# leitorcartao.net
KiCad netlist of a schematic drawn in EAGLE
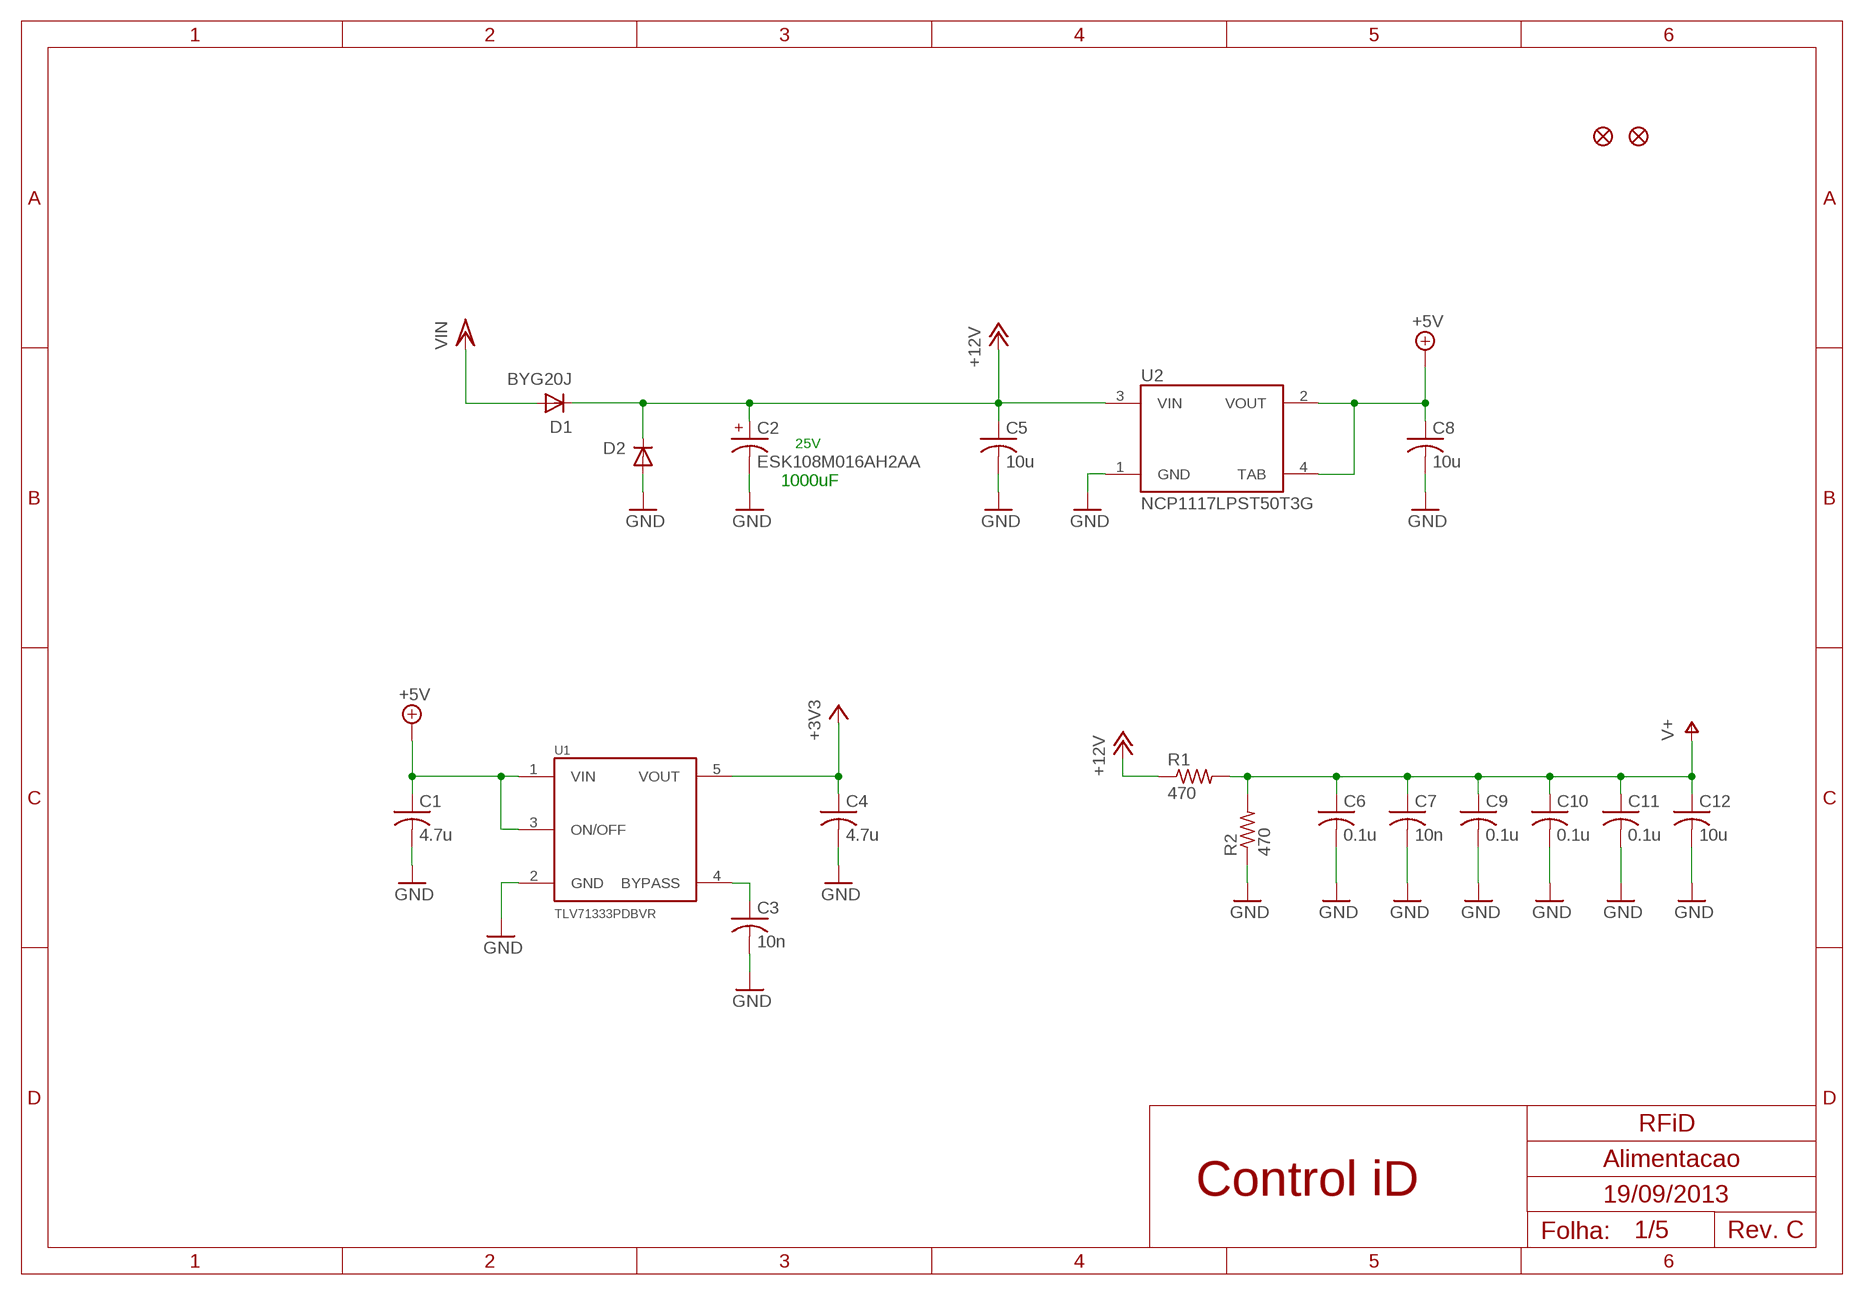
[diagram p0: schematic, sheet 1]
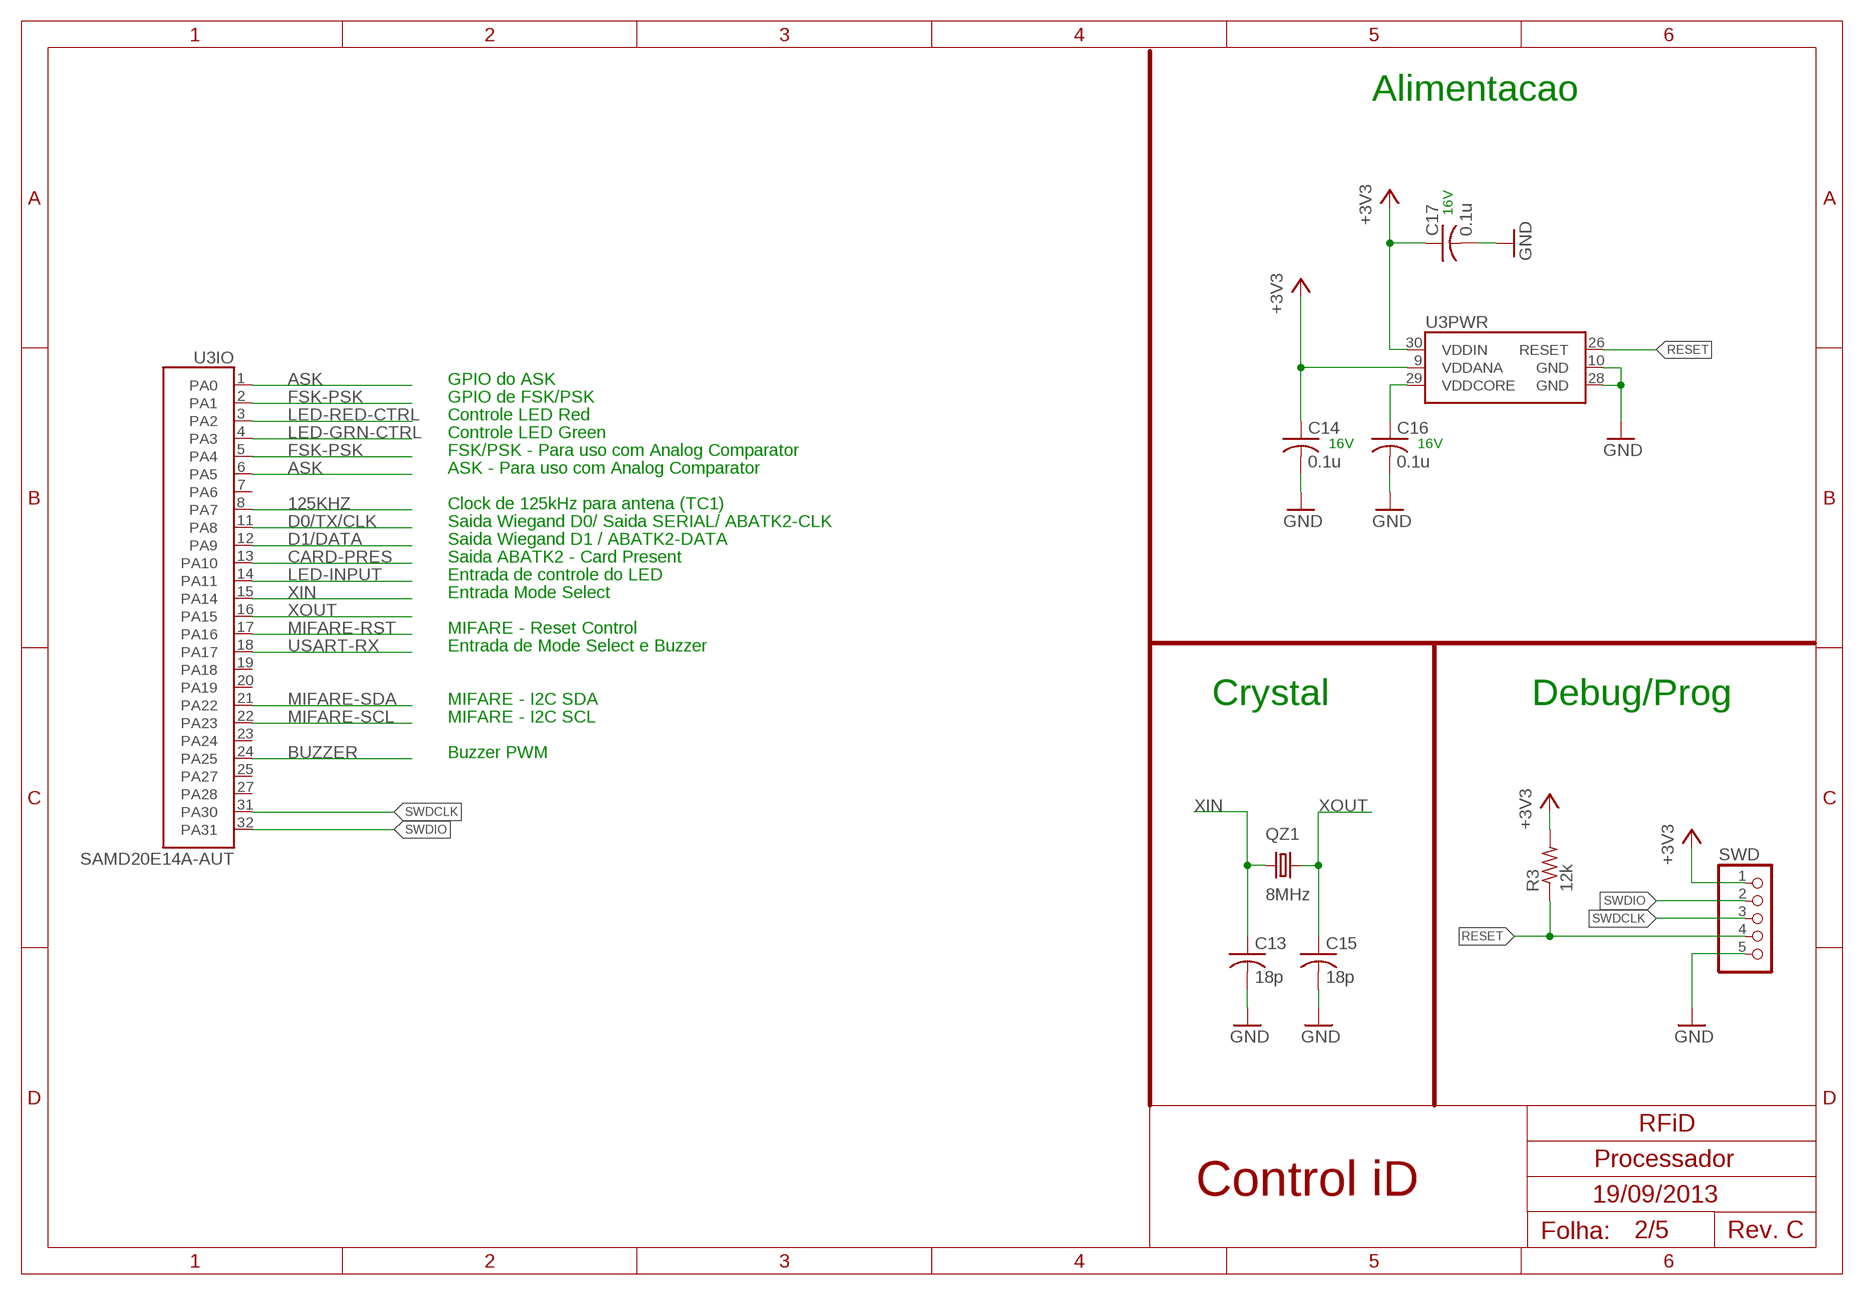
[diagram p1: schematic, sheet 2]
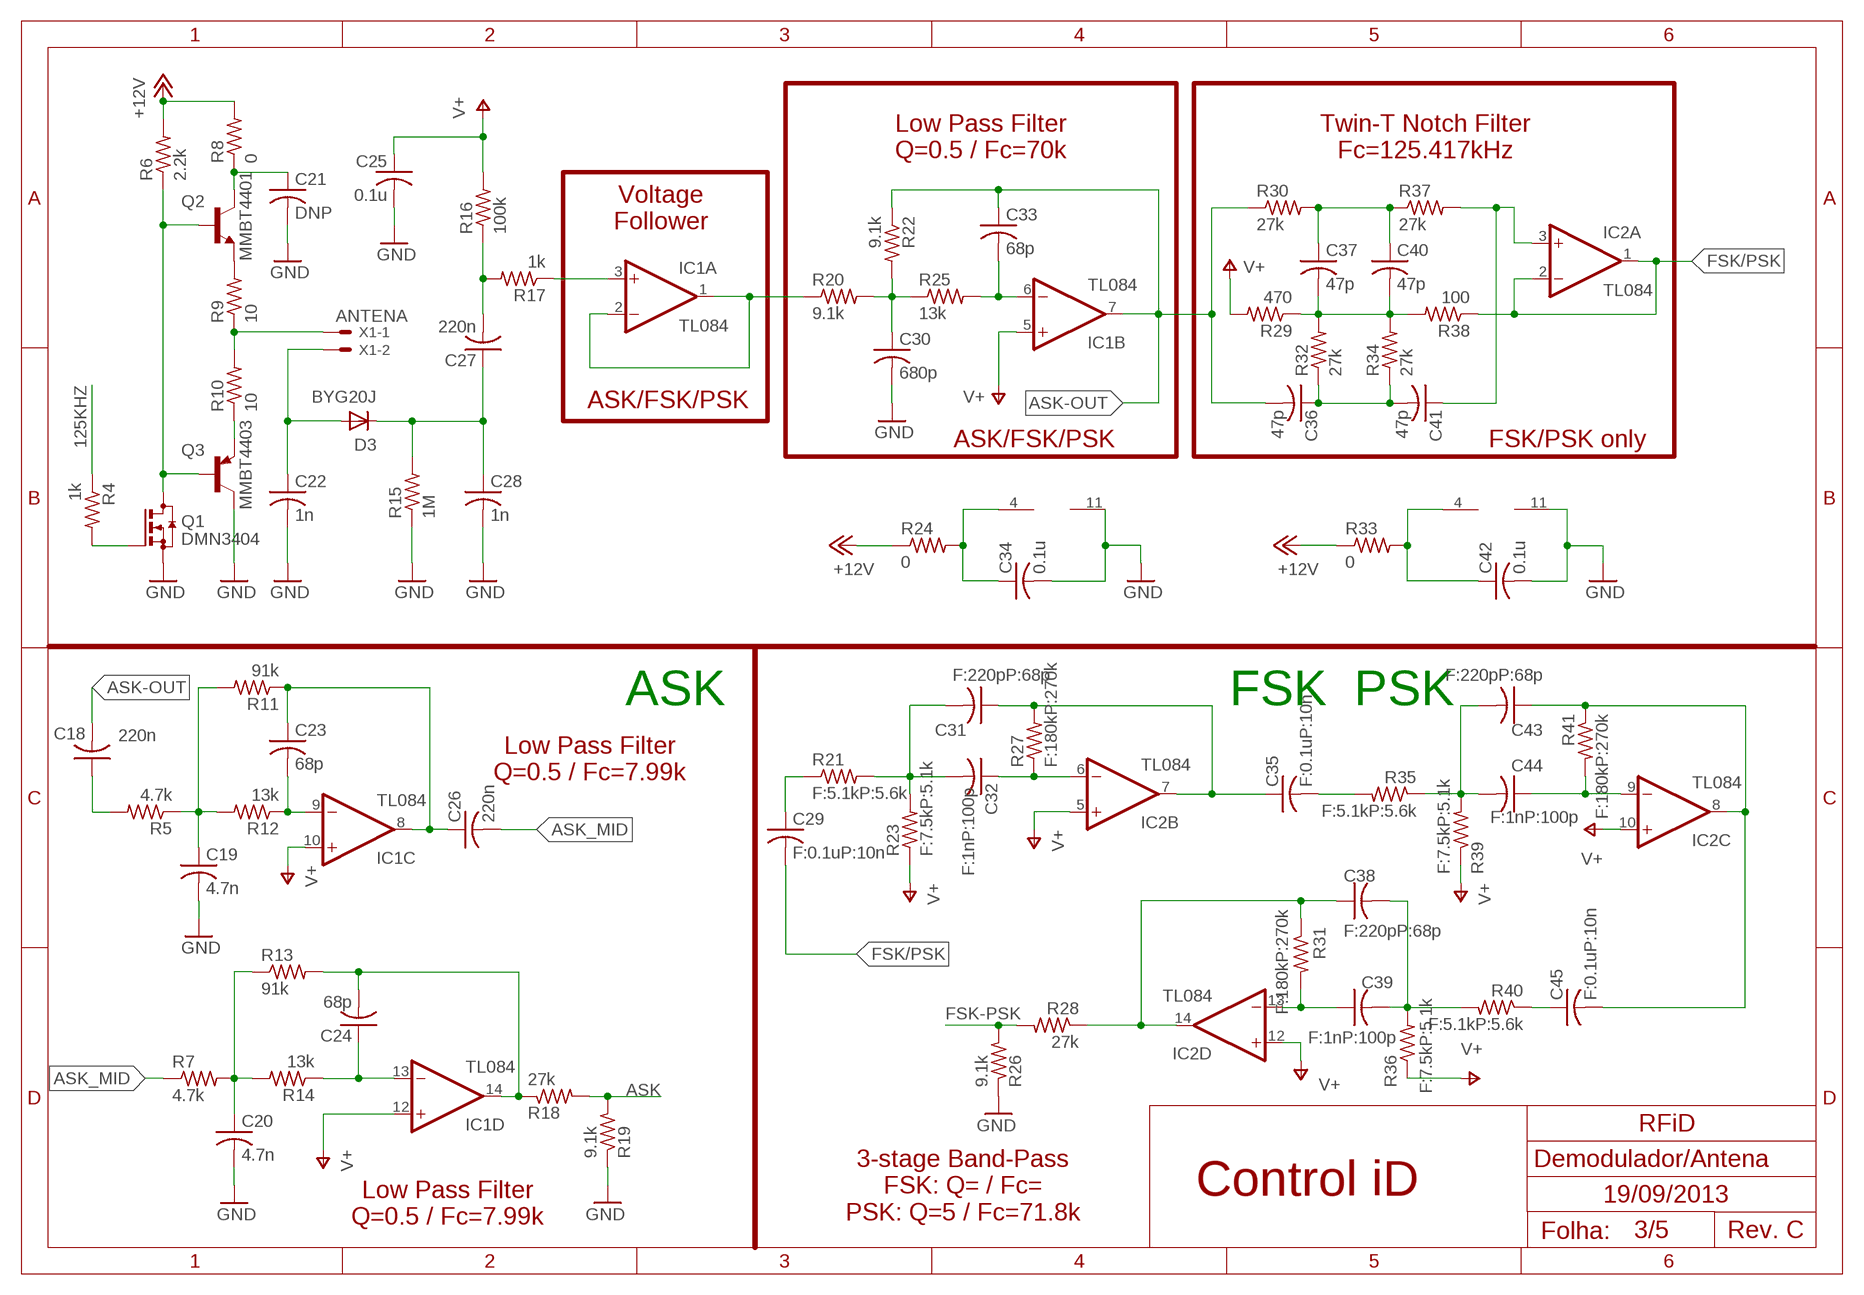
[diagram p2: schematic, sheet 3]
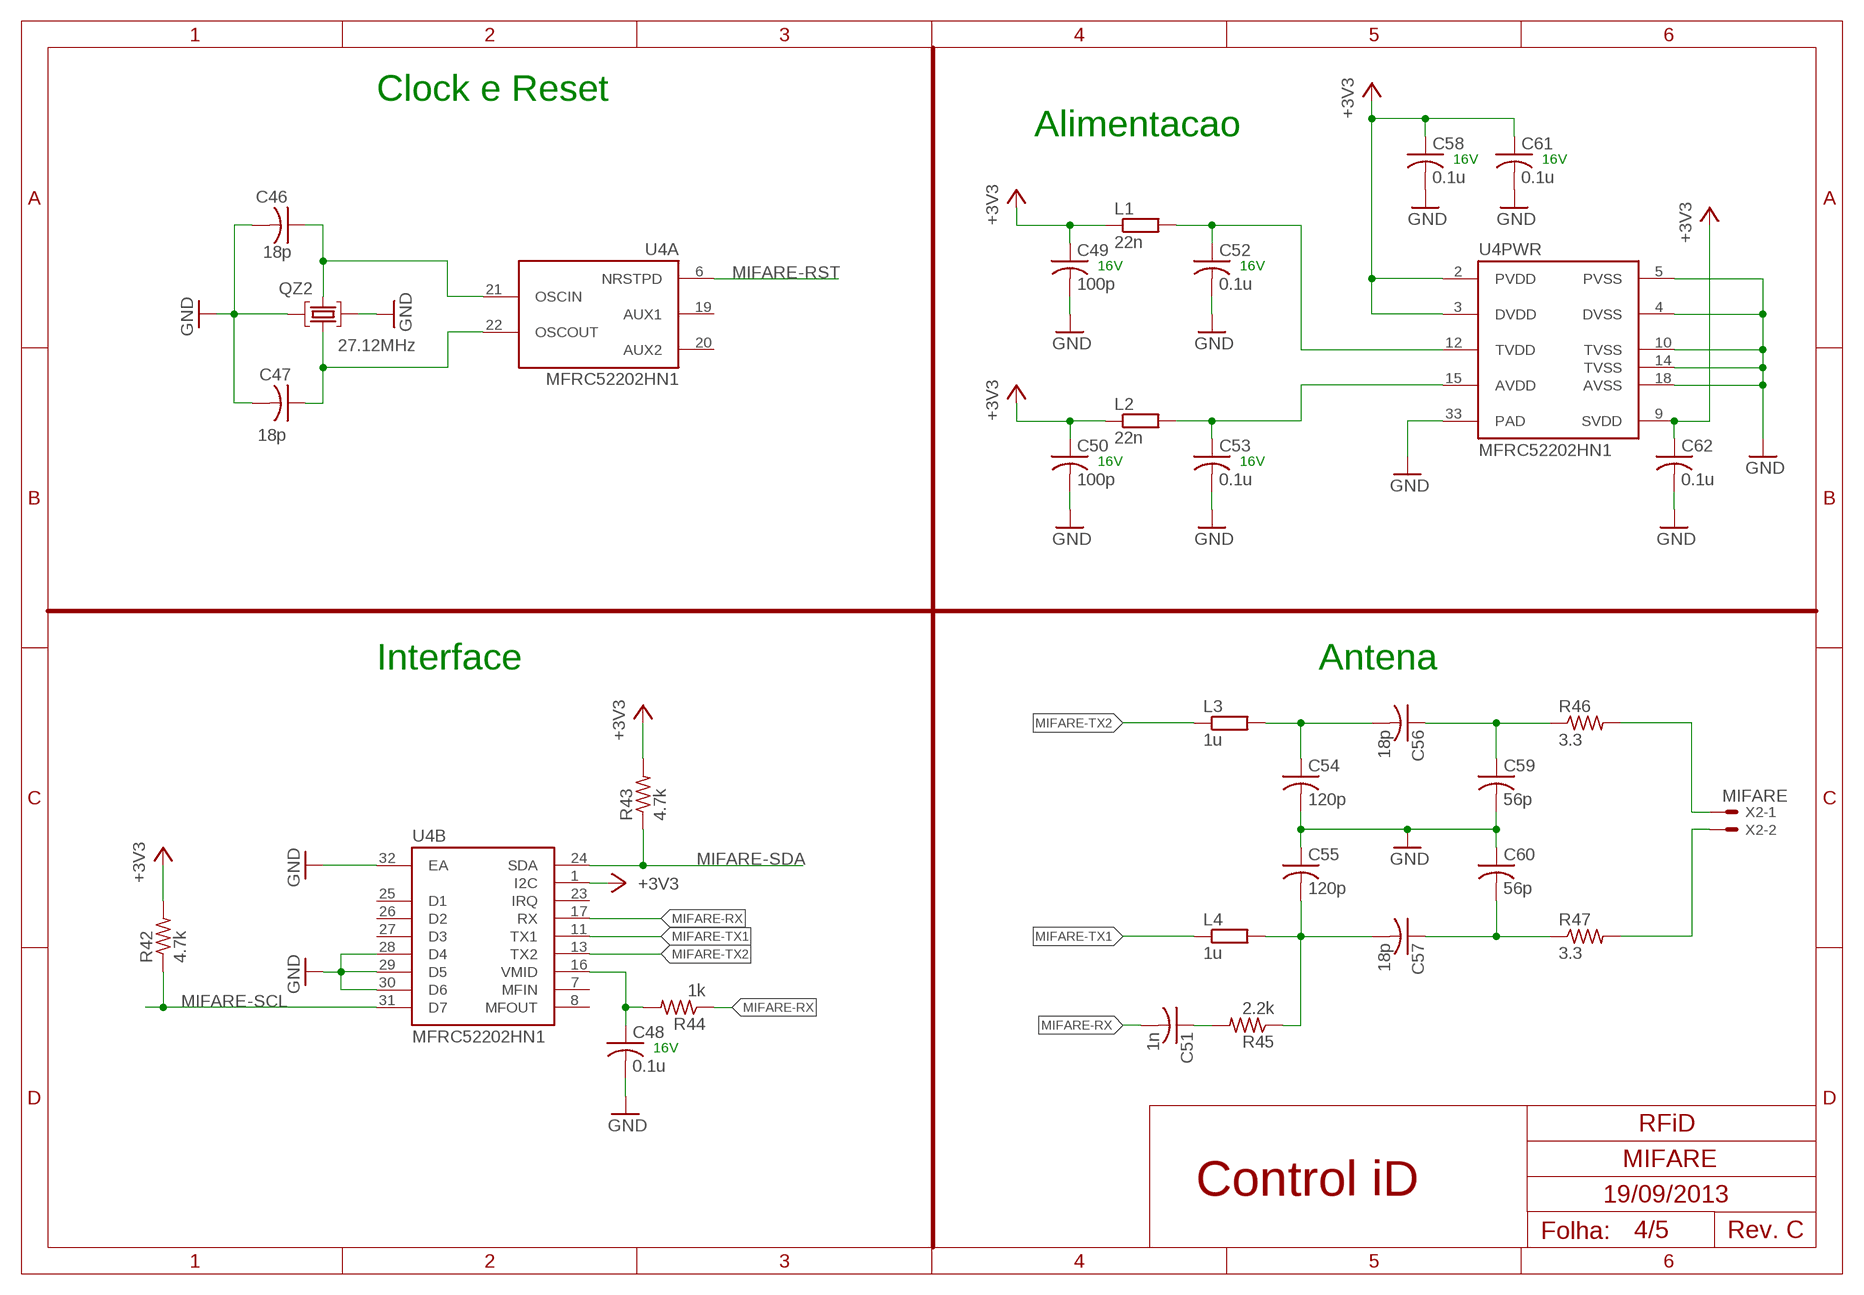
[diagram p3: schematic, sheet 4]
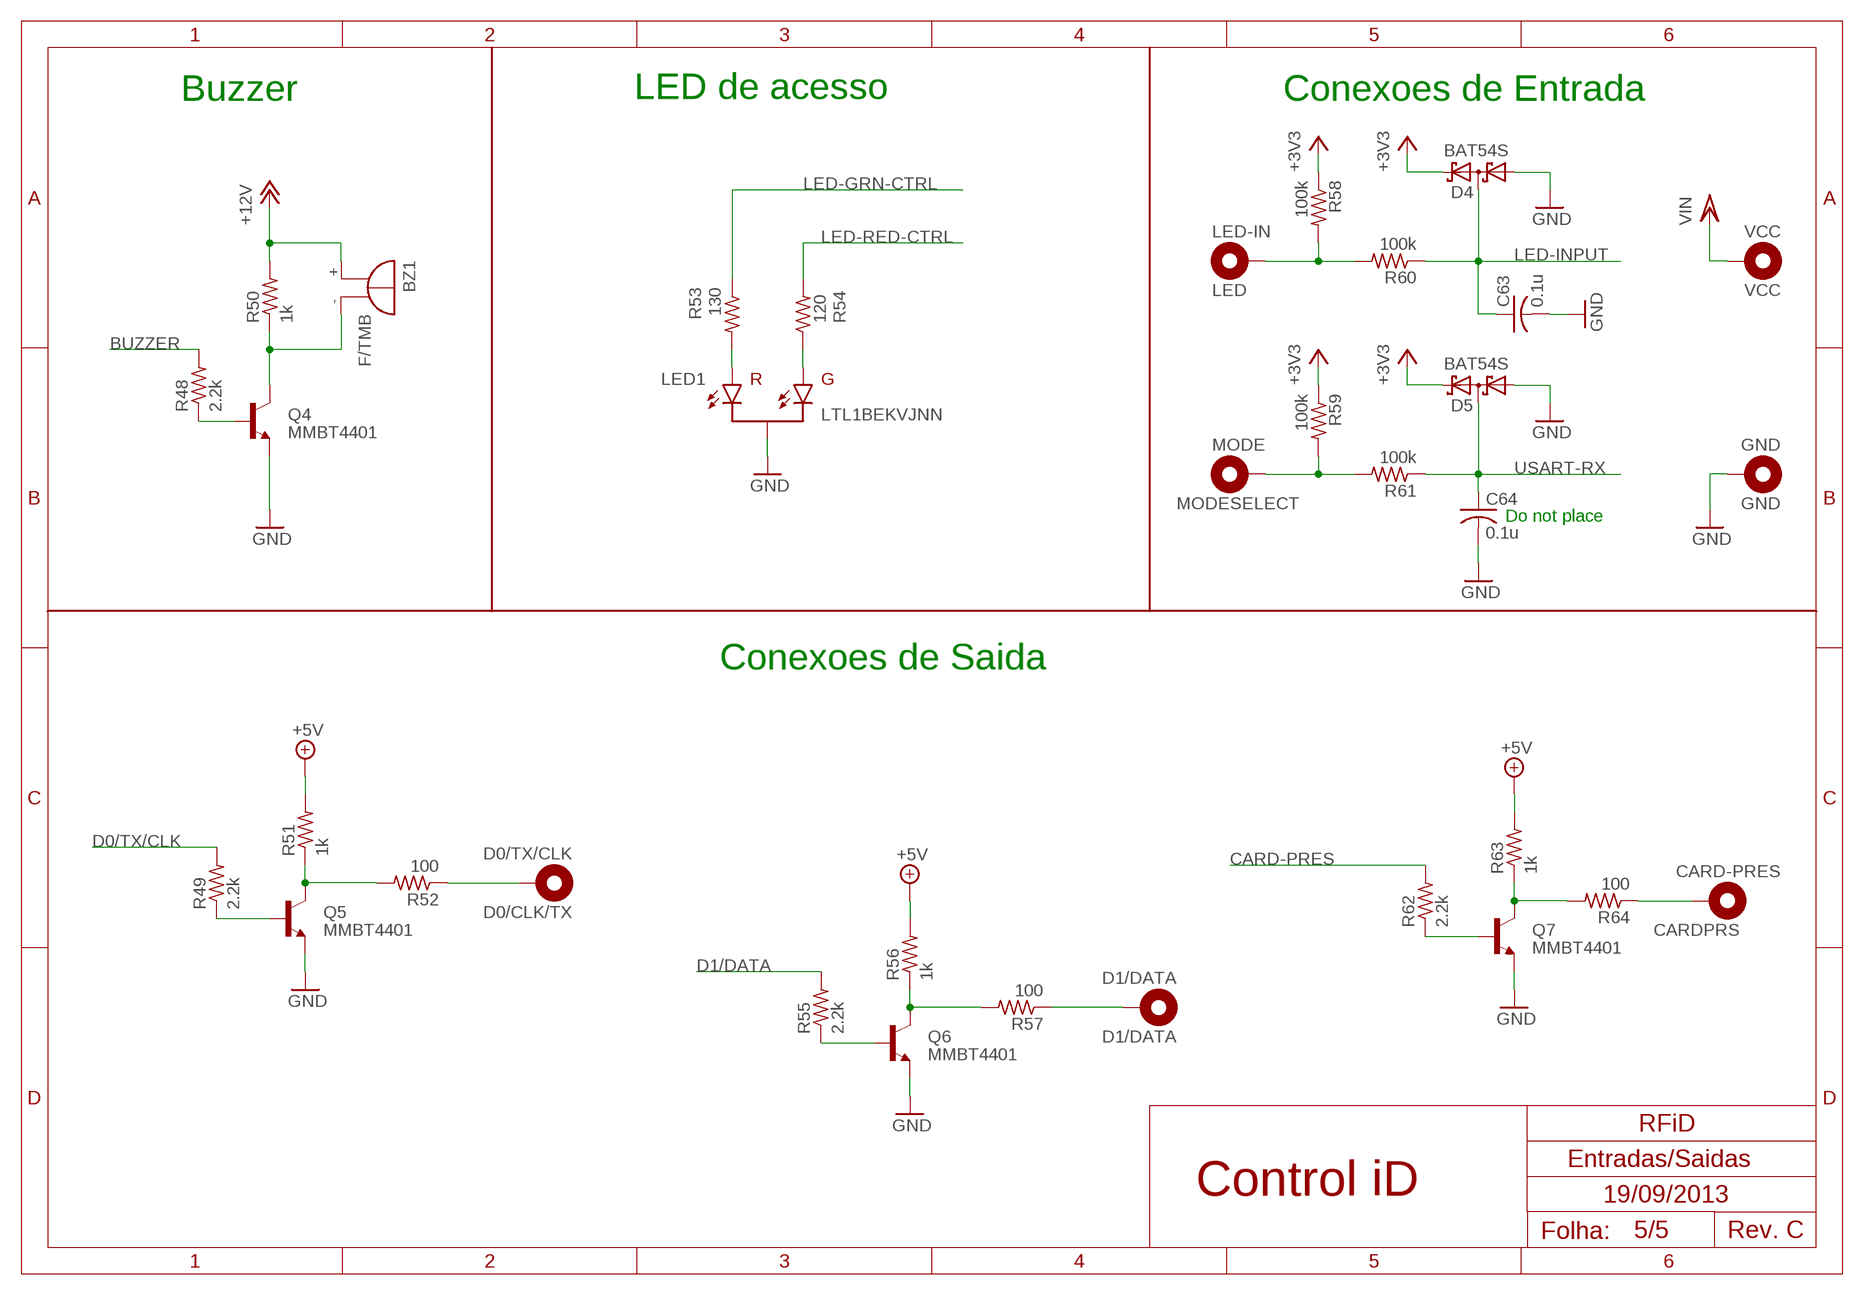
[diagram p4: schematic, sheet 5]

(export (version "E")
  (design (tool "Eeschema 10.0.6"))
  (components
    (comp (ref "BZ1")
      (value "F/TMB")
      (footprint "eagle-import:F_TMB")
      (libsource (lib "eagle-import") (part "F/TMB"))
    )
    (comp (ref "C63")
      (value "0.1u")
      (footprint "eagle-import:C0402")
      (libsource (lib "eagle-import") (part "C-USC0402"))
    )
    (comp (ref "C64")
      (value "0.1u")
      (footprint "eagle-import:C0402")
      (libsource (lib "eagle-import") (part "C-USC0402"))
    )
    (comp (ref "CARDPRS")
      (value "CARD-PRES")
      (footprint "eagle-import:HOLE")
      (libsource (lib "eagle-import") (part "PTHPAD"))
    )
    (comp (ref "D0/TX/CLK")
      (value "D0/CLK/TX")
      (footprint "eagle-import:HOLE")
      (libsource (lib "eagle-import") (part "PTHPAD"))
    )
    (comp (ref "D1/DATA")
      (value "D1/DATA")
      (footprint "eagle-import:HOLE")
      (libsource (lib "eagle-import") (part "PTHPAD"))
    )
    (comp (ref "D4")
      (value "BAT54S")
      (footprint "eagle-import:SOT23")
      (libsource (lib "eagle-import") (part "BAT54S"))
    )
    (comp (ref "D5")
      (value "BAT54S")
      (footprint "eagle-import:SOT23")
      (libsource (lib "eagle-import") (part "BAT54S"))
    )
    (comp (ref "GND")
      (value "GND")
      (footprint "eagle-import:HOLE")
      (libsource (lib "eagle-import") (part "PTHPAD"))
    )
    (comp (ref "LED-IN")
      (value "LED")
      (footprint "eagle-import:HOLE")
      (libsource (lib "eagle-import") (part "PTHPAD"))
    )
    (comp (ref "LED1")
      (value "LTL1BEKVJNN")
      (footprint "eagle-import:LTL1BEKVJNN")
      (libsource (lib "eagle-import") (part "LTL1BEKVJNN"))
    )
    (comp (ref "MODE")
      (value "MODESELECT")
      (footprint "eagle-import:HOLE")
      (libsource (lib "eagle-import") (part "PTHPAD"))
    )
    (comp (ref "Q4")
      (value "MMBT4401")
      (footprint "eagle-import:SOT23")
      (libsource (lib "eagle-import") (part "MMBT4401"))
    )
    (comp (ref "Q5")
      (value "MMBT4401")
      (footprint "eagle-import:SOT23")
      (libsource (lib "eagle-import") (part "MMBT4401"))
    )
    (comp (ref "Q6")
      (value "MMBT4401")
      (footprint "eagle-import:SOT23")
      (libsource (lib "eagle-import") (part "MMBT4401"))
    )
    (comp (ref "Q7")
      (value "MMBT4401")
      (footprint "eagle-import:SOT23")
      (libsource (lib "eagle-import") (part "MMBT4401"))
    )
    (comp (ref "R48")
      (value "2.2k")
      (footprint "eagle-import:R0402")
      (libsource (lib "eagle-import") (part "R-US_R0402"))
    )
    (comp (ref "R49")
      (value "2.2k")
      (footprint "eagle-import:R0402")
      (libsource (lib "eagle-import") (part "R-US_R0402"))
    )
    (comp (ref "R50")
      (value "1k")
      (footprint "eagle-import:R0402")
      (libsource (lib "eagle-import") (part "R-US_R0402"))
    )
    (comp (ref "R51")
      (value "1k")
      (footprint "eagle-import:R0402")
      (libsource (lib "eagle-import") (part "R-US_R0402"))
    )
    (comp (ref "R52")
      (value "100")
      (footprint "eagle-import:R0603")
      (libsource (lib "eagle-import") (part "R-US_R0603"))
    )
    (comp (ref "R53")
      (value "130")
      (footprint "eagle-import:R0402")
      (libsource (lib "eagle-import") (part "R-US_R0402"))
    )
    (comp (ref "R54")
      (value "120")
      (footprint "eagle-import:R0402")
      (libsource (lib "eagle-import") (part "R-US_R0402"))
    )
    (comp (ref "R55")
      (value "2.2k")
      (footprint "eagle-import:R0402")
      (libsource (lib "eagle-import") (part "R-US_R0402"))
    )
    (comp (ref "R56")
      (value "1k")
      (footprint "eagle-import:R0402")
      (libsource (lib "eagle-import") (part "R-US_R0402"))
    )
    (comp (ref "R57")
      (value "100")
      (footprint "eagle-import:R0603")
      (libsource (lib "eagle-import") (part "R-US_R0603"))
    )
    (comp (ref "R58")
      (value "100k")
      (footprint "eagle-import:R0603")
      (libsource (lib "eagle-import") (part "R-US_R0603"))
    )
    (comp (ref "R59")
      (value "100k")
      (footprint "eagle-import:R0603")
      (libsource (lib "eagle-import") (part "R-US_R0603"))
    )
    (comp (ref "R60")
      (value "100k")
      (footprint "eagle-import:R0603")
      (libsource (lib "eagle-import") (part "R-US_R0603"))
    )
    (comp (ref "R61")
      (value "100k")
      (footprint "eagle-import:R0603")
      (libsource (lib "eagle-import") (part "R-US_R0603"))
    )
    (comp (ref "R62")
      (value "2.2k")
      (footprint "eagle-import:R0402")
      (libsource (lib "eagle-import") (part "R-US_R0402"))
    )
    (comp (ref "R63")
      (value "1k")
      (footprint "eagle-import:R0402")
      (libsource (lib "eagle-import") (part "R-US_R0402"))
    )
    (comp (ref "R64")
      (value "100")
      (footprint "eagle-import:R0603")
      (libsource (lib "eagle-import") (part "R-US_R0603"))
    )
    (comp (ref "VCC")
      (value "VCC")
      (footprint "eagle-import:HOLE")
      (libsource (lib "eagle-import") (part "PTHPAD"))
    )
    (comp (ref "C46")
      (value "18p")
      (footprint "eagle-import:C0603")
      (libsource (lib "eagle-import") (part "C-USC0603"))
    )
    (comp (ref "C47")
      (value "18p")
      (footprint "eagle-import:C0603")
      (libsource (lib "eagle-import") (part "C-USC0603"))
    )
    (comp (ref "C48")
      (value "0.1u")
      (footprint "eagle-import:C0402")
      (libsource (lib "eagle-import") (part "C-USC0402"))
    )
    (comp (ref "C49")
      (value "100p")
      (footprint "eagle-import:C0402")
      (libsource (lib "eagle-import") (part "C-USC0402"))
    )
    (comp (ref "C50")
      (value "100p")
      (footprint "eagle-import:C0402")
      (libsource (lib "eagle-import") (part "C-USC0402"))
    )
    (comp (ref "C51")
      (value "1n")
      (footprint "eagle-import:C0402")
      (libsource (lib "eagle-import") (part "C-USC0402"))
    )
    (comp (ref "C52")
      (value "0.1u")
      (footprint "eagle-import:C0402")
      (libsource (lib "eagle-import") (part "C-USC0402"))
    )
    (comp (ref "C53")
      (value "0.1u")
      (footprint "eagle-import:C0402")
      (libsource (lib "eagle-import") (part "C-USC0402"))
    )
    (comp (ref "C54")
      (value "120p")
      (footprint "eagle-import:C0603")
      (libsource (lib "eagle-import") (part "C-USC0603"))
    )
    (comp (ref "C55")
      (value "120p")
      (footprint "eagle-import:C0603")
      (libsource (lib "eagle-import") (part "C-USC0603"))
    )
    (comp (ref "C56")
      (value "18p")
      (footprint "eagle-import:C0603")
      (libsource (lib "eagle-import") (part "C-USC0603"))
    )
    (comp (ref "C57")
      (value "18p")
      (footprint "eagle-import:C0603")
      (libsource (lib "eagle-import") (part "C-USC0603"))
    )
    (comp (ref "C58")
      (value "0.1u")
      (footprint "eagle-import:C0402")
      (libsource (lib "eagle-import") (part "C-USC0402"))
    )
    (comp (ref "C59")
      (value "56p")
      (footprint "eagle-import:C0603")
      (libsource (lib "eagle-import") (part "C-USC0603"))
    )
    (comp (ref "C60")
      (value "56p")
      (footprint "eagle-import:C0603")
      (libsource (lib "eagle-import") (part "C-USC0603"))
    )
    (comp (ref "C61")
      (value "0.1u")
      (footprint "eagle-import:C0402")
      (libsource (lib "eagle-import") (part "C-USC0402"))
    )
    (comp (ref "C62")
      (value "0.1u")
      (footprint "eagle-import:C0402")
      (libsource (lib "eagle-import") (part "C-USC0402"))
    )
    (comp (ref "L1")
      (value "22n")
      (footprint "eagle-import:R0402")
      (libsource (lib "eagle-import") (part "R-EU_R0402"))
    )
    (comp (ref "L2")
      (value "22n")
      (footprint "eagle-import:R0402")
      (libsource (lib "eagle-import") (part "R-EU_R0402"))
    )
    (comp (ref "L3")
      (value "1u")
      (footprint "eagle-import:R0603")
      (libsource (lib "eagle-import") (part "R-EU_R0603"))
    )
    (comp (ref "L4")
      (value "1u")
      (footprint "eagle-import:R0603")
      (libsource (lib "eagle-import") (part "R-EU_R0603"))
    )
    (comp (ref "QZ2")
      (value "27.12MHz")
      (footprint "eagle-import:CRISTAL4SMD")
      (libsource (lib "eagle-import") (part "CRISTAL"))
    )
    (comp (ref "R42")
      (value "4.7k")
      (footprint "eagle-import:R0402")
      (libsource (lib "eagle-import") (part "R-US_R0402"))
    )
    (comp (ref "R43")
      (value "4.7k")
      (footprint "eagle-import:R0402")
      (libsource (lib "eagle-import") (part "R-US_R0402"))
    )
    (comp (ref "R44")
      (value "1k")
      (footprint "eagle-import:R0402")
      (libsource (lib "eagle-import") (part "R-US_R0402"))
    )
    (comp (ref "R45")
      (value "2.2k")
      (footprint "eagle-import:R0402")
      (libsource (lib "eagle-import") (part "R-US_R0402"))
    )
    (comp (ref "R46")
      (value "3.3")
      (footprint "eagle-import:R0603")
      (libsource (lib "eagle-import") (part "R-US_R0603"))
    )
    (comp (ref "R47")
      (value "3.3")
      (footprint "eagle-import:R0603")
      (libsource (lib "eagle-import") (part "R-US_R0603"))
    )
    (comp (ref "U4")
      (value "MFRC52202HN1")
      (footprint "eagle-import:QFN32")
      (fields
        (field (name "MIFARE") "X")
        (field (name "MIFARE_CUSTOMERPN") "IC/MFRC52202")
        (field (name "MIFARE_PN") "MFRC52202HN1,151")
      )
      (libsource (lib "eagle-import") (part "MFRC52202HN1"))
    )
    (comp (ref "X2")
      (value "MIFARE")
      (footprint "eagle-import:ANTENNA")
      (libsource (lib "eagle-import") (part "ANTENA"))
    )
    (comp (ref "C1")
      (value "4.7u")
      (footprint "eagle-import:C0603")
      (libsource (lib "eagle-import") (part "C-USC0603"))
    )
    (comp (ref "C2")
      (value "ESK108M016AH2AA")
      (footprint "eagle-import:ESK108M016AH2AA")
      (libsource (lib "eagle-import") (part "ESK108M016AH2AA"))
    )
    (comp (ref "C3")
      (value "10n")
      (footprint "eagle-import:C0402")
      (libsource (lib "eagle-import") (part "C-USC0402"))
    )
    (comp (ref "C4")
      (value "4.7u")
      (footprint "eagle-import:C0603")
      (libsource (lib "eagle-import") (part "C-USC0603"))
    )
    (comp (ref "C5")
      (value "10u")
      (footprint "eagle-import:C0805")
      (libsource (lib "eagle-import") (part "C-USC0805"))
    )
    (comp (ref "C6")
      (value "0.1u")
      (footprint "eagle-import:C0402")
      (libsource (lib "eagle-import") (part "C-USC0402"))
    )
    (comp (ref "C7")
      (value "10n")
      (footprint "eagle-import:C0402")
      (libsource (lib "eagle-import") (part "C-USC0402"))
    )
    (comp (ref "C8")
      (value "10u")
      (footprint "eagle-import:C0805")
      (libsource (lib "eagle-import") (part "C-USC0805"))
    )
    (comp (ref "C9")
      (value "0.1u")
      (footprint "eagle-import:C0402")
      (libsource (lib "eagle-import") (part "C-USC0402"))
    )
    (comp (ref "C10")
      (value "0.1u")
      (footprint "eagle-import:C0402")
      (libsource (lib "eagle-import") (part "C-USC0402"))
    )
    (comp (ref "C11")
      (value "0.1u")
      (footprint "eagle-import:C0402")
      (libsource (lib "eagle-import") (part "C-USC0402"))
    )
    (comp (ref "C12")
      (value "10u")
      (footprint "eagle-import:C0805")
      (libsource (lib "eagle-import") (part "C-USC0805"))
    )
    (comp (ref "D1")
      (value "BYG20J")
      (footprint "eagle-import:SMA")
      (libsource (lib "eagle-import") (part "BYG20J"))
    )
    (comp (ref "D2")
      (value "DIODE-DO214AC")
      (footprint "eagle-import:DO214AC")
      (libsource (lib "eagle-import") (part "DIODE-DO214AC"))
    )
    (comp (ref "FID1")
      (value "FIDUCIAL1.5X3")
      (footprint "eagle-import:FIDUCIAL-1.5X3")
      (libsource (lib "eagle-import") (part "FIDUCIAL1.5X3"))
    )
    (comp (ref "FID3")
      (value "FIDUCIAL1.5X3")
      (footprint "eagle-import:FIDUCIAL-1.5X3")
      (libsource (lib "eagle-import") (part "FIDUCIAL1.5X3"))
    )
    (comp (ref "R1")
      (value "470")
      (footprint "eagle-import:R0402")
      (libsource (lib "eagle-import") (part "R-US_R0402"))
    )
    (comp (ref "R2")
      (value "470")
      (footprint "eagle-import:R0402")
      (libsource (lib "eagle-import") (part "R-US_R0402"))
    )
    (comp (ref "U1")
      (value "TLV71333PDBVR")
      (footprint "eagle-import:SOT-23-5")
      (libsource (lib "eagle-import") (part "LP2985-33DBVR"))
    )
    (comp (ref "U2")
      (value "NCP1117LPST50T3G")
      (footprint "eagle-import:SOT223-3L")
      (libsource (lib "eagle-import") (part "TLV1117-50CDCYR"))
    )
    (comp (ref "C18")
      (value "220n")
      (footprint "eagle-import:C0402")
      (libsource (lib "eagle-import") (part "C-USC0402"))
    )
    (comp (ref "C19")
      (value "4.7n")
      (footprint "eagle-import:C0402")
      (libsource (lib "eagle-import") (part "C-USC0402"))
    )
    (comp (ref "C20")
      (value "4.7n")
      (footprint "eagle-import:C0402")
      (libsource (lib "eagle-import") (part "C-USC0402"))
    )
    (comp (ref "C21")
      (value "DNP")
      (footprint "eagle-import:C0603")
      (libsource (lib "eagle-import") (part "C-USC0603"))
    )
    (comp (ref "C22")
      (value "1n")
      (footprint "eagle-import:C1812S")
      (libsource (lib "eagle-import") (part "C-USC1812S"))
    )
    (comp (ref "C23")
      (value "68p")
      (footprint "eagle-import:C0402")
      (libsource (lib "eagle-import") (part "C-USC0402"))
    )
    (comp (ref "C24")
      (value "68p")
      (footprint "eagle-import:C0402")
      (libsource (lib "eagle-import") (part "C-USC0402"))
    )
    (comp (ref "C25")
      (value "0.1u")
      (footprint "eagle-import:C0402")
      (libsource (lib "eagle-import") (part "C-USC0402"))
    )
    (comp (ref "C26")
      (value "220n")
      (footprint "eagle-import:C0402")
      (libsource (lib "eagle-import") (part "C-USC0402"))
    )
    (comp (ref "C27")
      (value "220n")
      (footprint "eagle-import:C1206S")
      (libsource (lib "eagle-import") (part "C-USC1206S"))
    )
    (comp (ref "C28")
      (value "1n")
      (footprint "eagle-import:C1206S")
      (libsource (lib "eagle-import") (part "C-USC1206S"))
    )
    (comp (ref "C29")
      (value "F:0.1uP:10n")
      (footprint "eagle-import:C0402")
      (libsource (lib "eagle-import") (part "C-USC0402"))
    )
    (comp (ref "C30")
      (value "680p")
      (footprint "eagle-import:C0402")
      (libsource (lib "eagle-import") (part "C-USC0402"))
    )
    (comp (ref "C31")
      (value "F:220pP:68p")
      (footprint "eagle-import:C0402")
      (libsource (lib "eagle-import") (part "C-USC0402"))
    )
    (comp (ref "C32")
      (value "F:1nP:100p")
      (footprint "eagle-import:C0402")
      (libsource (lib "eagle-import") (part "C-USC0402"))
    )
    (comp (ref "C33")
      (value "68p")
      (footprint "eagle-import:C0402")
      (libsource (lib "eagle-import") (part "C-USC0402"))
    )
    (comp (ref "C34")
      (value "0.1u")
      (footprint "eagle-import:C0402")
      (libsource (lib "eagle-import") (part "C-USC0402"))
    )
    (comp (ref "C35")
      (value "F:0.1uP:10n")
      (footprint "eagle-import:C0402")
      (libsource (lib "eagle-import") (part "C-USC0402"))
    )
    (comp (ref "C36")
      (value "47p")
      (footprint "eagle-import:C0402")
      (libsource (lib "eagle-import") (part "C-USC0402"))
    )
    (comp (ref "C37")
      (value "47p")
      (footprint "eagle-import:C0402")
      (libsource (lib "eagle-import") (part "C-USC0402"))
    )
    (comp (ref "C38")
      (value "F:220pP:68p")
      (footprint "eagle-import:C0402")
      (libsource (lib "eagle-import") (part "C-USC0402"))
    )
    (comp (ref "C39")
      (value "F:1nP:100p")
      (footprint "eagle-import:C0402")
      (libsource (lib "eagle-import") (part "C-USC0402"))
    )
    (comp (ref "C40")
      (value "47p")
      (footprint "eagle-import:C0402")
      (libsource (lib "eagle-import") (part "C-USC0402"))
    )
    (comp (ref "C41")
      (value "47p")
      (footprint "eagle-import:C0402")
      (libsource (lib "eagle-import") (part "C-USC0402"))
    )
    (comp (ref "C42")
      (value "0.1u")
      (footprint "eagle-import:C0402")
      (libsource (lib "eagle-import") (part "C-USC0402"))
    )
    (comp (ref "C43")
      (value "F:220pP:68p")
      (footprint "eagle-import:C0402")
      (libsource (lib "eagle-import") (part "C-USC0402"))
    )
    (comp (ref "C44")
      (value "F:1nP:100p")
      (footprint "eagle-import:C0402")
      (libsource (lib "eagle-import") (part "C-USC0402"))
    )
    (comp (ref "C45")
      (value "F:0.1uP:10n")
      (footprint "eagle-import:C0402")
      (libsource (lib "eagle-import") (part "C-USC0402"))
    )
    (comp (ref "D3")
      (value "BYG20J")
      (footprint "eagle-import:SMA")
      (libsource (lib "eagle-import") (part "BYG20J"))
    )
    (comp (ref "IC1")
      (value "TL084")
      (footprint "eagle-import:TSSOP14")
      (fields
        (field (name "ASK") "X")
        (field (name "ASK_CUSTOMERPN") "IC/TL084/TSSOP14")
        (field (name "ASK_PN") "TL084CPT")
        (field (name "FSK") "X")
        (field (name "FSK_CUSTOMERPN") "IC/TL084/TSSOP14")
        (field (name "FSK_PN") "TL084CPT")
        (field (name "MIFARE") "X")
        (field (name "MIFARE_CUSTOMERPN") "IC/TL084/TSSOP14")
        (field (name "MIFARE_PN") "TL084CPT")
        (field (name "PSK") "X")
        (field (name "PSK_CUSTOMERPN") "IC/TL084/TSSOP14")
        (field (name "PSK_PN") "TL084CPT")
      )
      (libsource (lib "eagle-import") (part "TL084"))
    )
    (comp (ref "IC2")
      (value "TL084")
      (footprint "eagle-import:TSSOP14")
      (fields
        (field (name "FSK") "X")
        (field (name "FSK_CUSTOMERPN") "IC/TL084/TSSOP14")
        (field (name "FSK_PN") "TL084CPT")
        (field (name "PSK") "X")
        (field (name "PSK_CUSTOMERPN") "IC/TL084/TSSOP14")
        (field (name "PSK_PN") "TL084CPT")
      )
      (libsource (lib "eagle-import") (part "TL084"))
    )
    (comp (ref "Q1")
      (value "DMN3404")
      (footprint "eagle-import:SOT23")
      (libsource (lib "eagle-import") (part "DMN3404"))
    )
    (comp (ref "Q2")
      (value "MMBT4401")
      (footprint "eagle-import:SOT23")
      (libsource (lib "eagle-import") (part "MMBT4401"))
    )
    (comp (ref "Q3")
      (value "MMBT4403")
      (footprint "eagle-import:SOT23")
      (libsource (lib "eagle-import") (part "MMBT4403"))
    )
    (comp (ref "R4")
      (value "1k")
      (footprint "eagle-import:R0402")
      (libsource (lib "eagle-import") (part "R-US_R0402"))
    )
    (comp (ref "R5")
      (value "4.7k")
      (footprint "eagle-import:R0402")
      (libsource (lib "eagle-import") (part "R-US_R0402"))
    )
    (comp (ref "R6")
      (value "2.2k")
      (footprint "eagle-import:R0402")
      (libsource (lib "eagle-import") (part "R-US_R0402"))
    )
    (comp (ref "R7")
      (value "4.7k")
      (footprint "eagle-import:R0402")
      (libsource (lib "eagle-import") (part "R-US_R0402"))
    )
    (comp (ref "R8")
      (value "0")
      (footprint "eagle-import:R0402")
      (libsource (lib "eagle-import") (part "R-US_R0402"))
    )
    (comp (ref "R9")
      (value "10")
      (footprint "eagle-import:R0603")
      (libsource (lib "eagle-import") (part "R-US_R0603"))
    )
    (comp (ref "R10")
      (value "10")
      (footprint "eagle-import:R0603")
      (libsource (lib "eagle-import") (part "R-US_R0603"))
    )
    (comp (ref "R11")
      (value "91k")
      (footprint "eagle-import:R0402")
      (libsource (lib "eagle-import") (part "R-US_R0402"))
    )
    (comp (ref "R12")
      (value "13k")
      (footprint "eagle-import:R0402")
      (libsource (lib "eagle-import") (part "R-US_R0402"))
    )
    (comp (ref "R13")
      (value "91k")
      (footprint "eagle-import:R0402")
      (libsource (lib "eagle-import") (part "R-US_R0402"))
    )
    (comp (ref "R14")
      (value "13k")
      (footprint "eagle-import:R0402")
      (libsource (lib "eagle-import") (part "R-US_R0402"))
    )
    (comp (ref "R15")
      (value "1M")
      (footprint "eagle-import:R1206S")
      (libsource (lib "eagle-import") (part "R-US_R1206S"))
    )
    (comp (ref "R16")
      (value "100k")
      (footprint "eagle-import:R0603")
      (libsource (lib "eagle-import") (part "R-US_R0603"))
    )
    (comp (ref "R17")
      (value "1k")
      (footprint "eagle-import:R0402")
      (libsource (lib "eagle-import") (part "R-US_R0402"))
    )
    (comp (ref "R18")
      (value "27k")
      (footprint "eagle-import:R0402")
      (libsource (lib "eagle-import") (part "R-US_R0402"))
    )
    (comp (ref "R19")
      (value "9.1k")
      (footprint "eagle-import:R0402")
      (libsource (lib "eagle-import") (part "R-US_R0402"))
    )
    (comp (ref "R20")
      (value "9.1k")
      (footprint "eagle-import:R0402")
      (libsource (lib "eagle-import") (part "R-US_R0402"))
    )
    (comp (ref "R21")
      (value "F:5.1kP:5.6k")
      (footprint "eagle-import:R0402")
      (libsource (lib "eagle-import") (part "R-US_R0402"))
    )
    (comp (ref "R22")
      (value "9.1k")
      (footprint "eagle-import:R0402")
      (libsource (lib "eagle-import") (part "R-US_R0402"))
    )
    (comp (ref "R23")
      (value "F:7.5kP:5.1k")
      (footprint "eagle-import:R0402")
      (libsource (lib "eagle-import") (part "R-US_R0402"))
    )
    (comp (ref "R24")
      (value "0")
      (footprint "eagle-import:R0402")
      (libsource (lib "eagle-import") (part "R-US_R0402"))
    )
    (comp (ref "R25")
      (value "13k")
      (footprint "eagle-import:R0402")
      (libsource (lib "eagle-import") (part "R-US_R0402"))
    )
    (comp (ref "R26")
      (value "9.1k")
      (footprint "eagle-import:R0402")
      (libsource (lib "eagle-import") (part "R-US_R0402"))
    )
    (comp (ref "R27")
      (value "F:180kP:270k")
      (footprint "eagle-import:R0402")
      (libsource (lib "eagle-import") (part "R-US_R0402"))
    )
    (comp (ref "R28")
      (value "27k")
      (footprint "eagle-import:R0402")
      (libsource (lib "eagle-import") (part "R-US_R0402"))
    )
    (comp (ref "R29")
      (value "470")
      (footprint "eagle-import:R0402")
      (libsource (lib "eagle-import") (part "R-US_R0402"))
    )
    (comp (ref "R30")
      (value "27k")
      (footprint "eagle-import:R0402")
      (libsource (lib "eagle-import") (part "R-US_R0402"))
    )
    (comp (ref "R31")
      (value "F:180kP:270k")
      (footprint "eagle-import:R0402")
      (libsource (lib "eagle-import") (part "R-US_R0402"))
    )
    (comp (ref "R32")
      (value "27k")
      (footprint "eagle-import:R0402")
      (libsource (lib "eagle-import") (part "R-US_R0402"))
    )
    (comp (ref "R33")
      (value "0")
      (footprint "eagle-import:R0402")
      (libsource (lib "eagle-import") (part "R-US_R0402"))
    )
    (comp (ref "R34")
      (value "27k")
      (footprint "eagle-import:R0402")
      (libsource (lib "eagle-import") (part "R-US_R0402"))
    )
    (comp (ref "R35")
      (value "F:5.1kP:5.6k")
      (footprint "eagle-import:R0402")
      (libsource (lib "eagle-import") (part "R-US_R0402"))
    )
    (comp (ref "R36")
      (value "F:7.5kP:5.1k")
      (footprint "eagle-import:R0402")
      (libsource (lib "eagle-import") (part "R-US_R0402"))
    )
    (comp (ref "R37")
      (value "27k")
      (footprint "eagle-import:R0402")
      (libsource (lib "eagle-import") (part "R-US_R0402"))
    )
    (comp (ref "R38")
      (value "100")
      (footprint "eagle-import:R0603")
      (libsource (lib "eagle-import") (part "R-US_R0603"))
    )
    (comp (ref "R39")
      (value "F:7.5kP:5.1k")
      (footprint "eagle-import:R0402")
      (libsource (lib "eagle-import") (part "R-US_R0402"))
    )
    (comp (ref "R40")
      (value "F:5.1kP:5.6k")
      (footprint "eagle-import:R0402")
      (libsource (lib "eagle-import") (part "R-US_R0402"))
    )
    (comp (ref "R41")
      (value "F:180kP:270k")
      (footprint "eagle-import:R0402")
      (libsource (lib "eagle-import") (part "R-US_R0402"))
    )
    (comp (ref "X1")
      (value "ANTENA")
      (footprint "eagle-import:22-23-2021")
      (libsource (lib "eagle-import") (part "22-23-2021"))
    )
    (comp (ref "C13")
      (value "18p")
      (footprint "eagle-import:C0603")
      (libsource (lib "eagle-import") (part "C-USC0603"))
    )
    (comp (ref "C14")
      (value "0.1u")
      (footprint "eagle-import:C0402")
      (libsource (lib "eagle-import") (part "C-USC0402"))
    )
    (comp (ref "C15")
      (value "18p")
      (footprint "eagle-import:C0603")
      (libsource (lib "eagle-import") (part "C-USC0603"))
    )
    (comp (ref "C16")
      (value "0.1u")
      (footprint "eagle-import:C0402")
      (libsource (lib "eagle-import") (part "C-USC0402"))
    )
    (comp (ref "C17")
      (value "0.1u")
      (footprint "eagle-import:C0402")
      (libsource (lib "eagle-import") (part "C-USC0402"))
    )
    (comp (ref "QZ1")
      (value "8MHz")
      (footprint "eagle-import:HC49_S")
      (libsource (lib "eagle-import") (part "CRYSTALHC49S"))
    )
    (comp (ref "R3")
      (value "12k")
      (footprint "eagle-import:R0402")
      (libsource (lib "eagle-import") (part "R-US_R0402"))
    )
    (comp (ref "SWD")
      (value "PINHD-1X5")
      (footprint "eagle-import:1X05")
      (libsource (lib "eagle-import") (part "PINHD-1X5"))
    )
    (comp (ref "U3")
      (value "SAMD20E14A-AUT")
      (footprint "eagle-import:TQFP32")
      (fields
        (field (name "ASK") "X")
        (field (name "ASK_CUSTOMERPN") "IC/SAMD20/TQ32")
        (field (name "ASK_PN") "SAMD20E14A-AUT")
        (field (name "FSK") "X")
        (field (name "FSK_CUSTOMERPN") "IC/SAMD20/TQ32")
        (field (name "FSK_PN") "SAMD20E14A-AUT")
        (field (name "MIFARE") "X")
        (field (name "MIFARE_CUSTOMERPN") "IC/SAMD20/TQ32")
        (field (name "MIFARE_PN") "SAMD20E14A-AUT")
        (field (name "PSK") "X")
        (field (name "PSK_CUSTOMERPN") "IC/SAMD20/TQ32")
        (field (name "PSK_PN") "SAMD20E14A-AUT")
      )
      (libsource (lib "eagle-import") (part "SAMD20E14A-AUT"))
    )
  )
  (nets
    (net (code "1") (name "+3V3") (class "Default")
      (node (ref "C14") (pin "1") (pinfunction "1_1") (pintype "passive"))
      (node (ref "C17") (pin "1") (pinfunction "1_1") (pintype "passive"))
      (node (ref "C4") (pin "1") (pinfunction "1_1") (pintype "passive"))
      (node (ref "C49") (pin "1") (pinfunction "1_1") (pintype "passive"))
      (node (ref "C50") (pin "1") (pinfunction "1_1") (pintype "passive"))
      (node (ref "C58") (pin "1") (pinfunction "1_1") (pintype "passive"))
      (node (ref "C61") (pin "1") (pinfunction "1_1") (pintype "passive"))
      (node (ref "C62") (pin "1") (pinfunction "1_1") (pintype "passive"))
      (node (ref "D4") (pin "2") (pinfunction "C2_2") (pintype "passive"))
      (node (ref "D5") (pin "2") (pinfunction "C2_2") (pintype "passive"))
      (node (ref "L1") (pin "1") (pinfunction "1_1") (pintype "passive"))
      (node (ref "L2") (pin "1") (pinfunction "1_1") (pintype "passive"))
      (node (ref "R3") (pin "2") (pinfunction "2_2") (pintype "passive"))
      (node (ref "R42") (pin "2") (pinfunction "2_2") (pintype "passive"))
      (node (ref "R43") (pin "2") (pinfunction "2_2") (pintype "passive"))
      (node (ref "R58") (pin "1") (pinfunction "1_1") (pintype "passive"))
      (node (ref "R59") (pin "1") (pinfunction "1_1") (pintype "passive"))
      (node (ref "SWD") (pin "1") (pinfunction "1_1") (pintype "passive"))
      (node (ref "U1") (pin "5") (pinfunction "VOUT_5") (pintype "bidirectional"))
      (node (ref "U3") (pin "30") (pinfunction "VDDIN_30") (pintype "power_in"))
      (node (ref "U3") (pin "9") (pinfunction "VDDANA_9") (pintype "power_in"))
      (node (ref "U4") (pin "1") (pinfunction "I2C_1") (pintype "bidirectional"))
      (node (ref "U4") (pin "2") (pinfunction "PVDD_2") (pintype "bidirectional"))
      (node (ref "U4") (pin "3") (pinfunction "DVDD_3") (pintype "bidirectional"))
      (node (ref "U4") (pin "9") (pinfunction "SVDD_9") (pintype "bidirectional"))
    )
    (net (code "2") (name "+5V") (class "Default")
      (node (ref "C1") (pin "1") (pinfunction "1_1") (pintype "passive"))
      (node (ref "C8") (pin "1") (pinfunction "1_1") (pintype "passive"))
      (node (ref "R51") (pin "2") (pinfunction "2_2") (pintype "passive"))
      (node (ref "R56") (pin "2") (pinfunction "2_2") (pintype "passive"))
      (node (ref "R63") (pin "2") (pinfunction "2_2") (pintype "passive"))
      (node (ref "U1") (pin "1") (pinfunction "VIN_1") (pintype "bidirectional"))
      (node (ref "U1") (pin "3") (pinfunction "ON/OFF_3") (pintype "bidirectional"))
      (node (ref "U2") (pin "2") (pinfunction "VOUT_2") (pintype "bidirectional"))
      (node (ref "U2") (pin "4") (pinfunction "TAB_4") (pintype "bidirectional"))
    )
    (net (code "3") (name "+12V") (class "Default")
      (node (ref "BZ1") (pin "+") (pinfunction "+_+") (pintype "passive"))
      (node (ref "C2") (pin "+") (pinfunction "+_+") (pintype "passive"))
      (node (ref "C5") (pin "1") (pinfunction "1_1") (pintype "passive"))
      (node (ref "D1") (pin "K") (pinfunction "K_K") (pintype "passive"))
      (node (ref "D2") (pin "C") (pinfunction "C_C") (pintype "passive"))
      (node (ref "R1") (pin "1") (pinfunction "1_1") (pintype "passive"))
      (node (ref "R24") (pin "1") (pinfunction "1_1") (pintype "passive"))
      (node (ref "R33") (pin "1") (pinfunction "1_1") (pintype "passive"))
      (node (ref "R50") (pin "2") (pinfunction "2_2") (pintype "passive"))
      (node (ref "R6") (pin "2") (pinfunction "2_2") (pintype "passive"))
      (node (ref "R8") (pin "2") (pinfunction "2_2") (pintype "passive"))
      (node (ref "U2") (pin "3") (pinfunction "VIN_3") (pintype "bidirectional"))
    )
    (net (code "4") (name "125KHZ") (class "Default")
      (node (ref "R4") (pin "1") (pinfunction "1_1") (pintype "passive"))
      (node (ref "U3") (pin "8") (pinfunction "PA7_8") (pintype "bidirectional"))
    )
    (net (code "5") (name "ASK") (class "Default")
      (node (ref "R18") (pin "2") (pinfunction "2_2") (pintype "passive"))
      (node (ref "R19") (pin "2") (pinfunction "2_2") (pintype "passive"))
      (node (ref "U3") (pin "1") (pinfunction "PA0_1") (pintype "bidirectional"))
      (node (ref "U3") (pin "6") (pinfunction "PA5_6") (pintype "bidirectional"))
    )
    (net (code "6") (name "ASK-OUT") (class "Default")
      (node (ref "C18") (pin "2") (pinfunction "2_2") (pintype "passive"))
      (node (ref "C33") (pin "1") (pinfunction "1_1") (pintype "passive"))
      (node (ref "C36") (pin "2") (pinfunction "2_2") (pintype "passive"))
      (node (ref "IC1") (pin "7") (pinfunction "OUT_7") (pintype "output"))
      (node (ref "R22") (pin "1") (pinfunction "1_1") (pintype "passive"))
      (node (ref "R30") (pin "1") (pinfunction "1_1") (pintype "passive"))
    )
    (net (code "7") (name "ASK_MID") (class "Default")
      (node (ref "C26") (pin "2") (pinfunction "2_2") (pintype "passive"))
      (node (ref "R7") (pin "1") (pinfunction "1_1") (pintype "passive"))
    )
    (net (code "8") (name "BUZZER") (class "Default")
      (node (ref "R48") (pin "2") (pinfunction "2_2") (pintype "passive"))
      (node (ref "U3") (pin "24") (pinfunction "PA25_24") (pintype "bidirectional"))
    )
    (net (code "9") (name "CARD-PRES") (class "Default")
      (node (ref "R62") (pin "2") (pinfunction "2_2") (pintype "passive"))
      (node (ref "U3") (pin "13") (pinfunction "PA10_13") (pintype "bidirectional"))
    )
    (net (code "10") (name "D0{slash}TX{slash}CLK") (class "Default")
      (node (ref "R49") (pin "2") (pinfunction "2_2") (pintype "passive"))
      (node (ref "U3") (pin "11") (pinfunction "PA8_11") (pintype "bidirectional"))
    )
    (net (code "11") (name "D1{slash}DATA") (class "Default")
      (node (ref "R55") (pin "2") (pinfunction "2_2") (pintype "passive"))
      (node (ref "U3") (pin "12") (pinfunction "PA9_12") (pintype "bidirectional"))
    )
    (net (code "12") (name "FSK-PSK") (class "Default")
      (node (ref "R26") (pin "2") (pinfunction "2_2") (pintype "passive"))
      (node (ref "R28") (pin "2") (pinfunction "2_2") (pintype "passive"))
      (node (ref "U3") (pin "2") (pinfunction "PA1_2") (pintype "bidirectional"))
      (node (ref "U3") (pin "5") (pinfunction "PA4_5") (pintype "bidirectional"))
    )
    (net (code "13") (name "FSK{slash}PSK") (class "Default")
      (node (ref "C29") (pin "2") (pinfunction "2_2") (pintype "passive"))
      (node (ref "IC2") (pin "1") (pinfunction "OUT_1") (pintype "output"))
      (node (ref "IC2") (pin "2") (pinfunction "-IN_2") (pintype "input"))
      (node (ref "R38") (pin "1") (pinfunction "1_1") (pintype "passive"))
    )
    (net (code "14") (name "GND") (class "Default")
      (node (ref "C1") (pin "2") (pinfunction "2_2") (pintype "passive"))
      (node (ref "C10") (pin "2") (pinfunction "2_2") (pintype "passive"))
      (node (ref "C11") (pin "2") (pinfunction "2_2") (pintype "passive"))
      (node (ref "C12") (pin "2") (pinfunction "2_2") (pintype "passive"))
      (node (ref "C13") (pin "2") (pinfunction "2_2") (pintype "passive"))
      (node (ref "C14") (pin "2") (pinfunction "2_2") (pintype "passive"))
      (node (ref "C15") (pin "2") (pinfunction "2_2") (pintype "passive"))
      (node (ref "C16") (pin "2") (pinfunction "2_2") (pintype "passive"))
      (node (ref "C17") (pin "2") (pinfunction "2_2") (pintype "passive"))
      (node (ref "C19") (pin "2") (pinfunction "2_2") (pintype "passive"))
      (node (ref "C2") (pin "-") (pinfunction "-_-") (pintype "passive"))
      (node (ref "C20") (pin "2") (pinfunction "2_2") (pintype "passive"))
      (node (ref "C21") (pin "2") (pinfunction "2_2") (pintype "passive"))
      (node (ref "C22") (pin "2") (pinfunction "2_2") (pintype "passive"))
      (node (ref "C25") (pin "2") (pinfunction "2_2") (pintype "passive"))
      (node (ref "C28") (pin "2") (pinfunction "2_2") (pintype "passive"))
      (node (ref "C3") (pin "2") (pinfunction "2_2") (pintype "passive"))
      (node (ref "C30") (pin "2") (pinfunction "2_2") (pintype "passive"))
      (node (ref "C34") (pin "2") (pinfunction "2_2") (pintype "passive"))
      (node (ref "C4") (pin "2") (pinfunction "2_2") (pintype "passive"))
      (node (ref "C42") (pin "2") (pinfunction "2_2") (pintype "passive"))
      (node (ref "C46") (pin "2") (pinfunction "2_2") (pintype "passive"))
      (node (ref "C47") (pin "2") (pinfunction "2_2") (pintype "passive"))
      (node (ref "C48") (pin "2") (pinfunction "2_2") (pintype "passive"))
      (node (ref "C49") (pin "2") (pinfunction "2_2") (pintype "passive"))
      (node (ref "C5") (pin "2") (pinfunction "2_2") (pintype "passive"))
      (node (ref "C50") (pin "2") (pinfunction "2_2") (pintype "passive"))
      (node (ref "C52") (pin "2") (pinfunction "2_2") (pintype "passive"))
      (node (ref "C53") (pin "2") (pinfunction "2_2") (pintype "passive"))
      (node (ref "C54") (pin "2") (pinfunction "2_2") (pintype "passive"))
      (node (ref "C55") (pin "1") (pinfunction "1_1") (pintype "passive"))
      (node (ref "C58") (pin "2") (pinfunction "2_2") (pintype "passive"))
      (node (ref "C59") (pin "2") (pinfunction "2_2") (pintype "passive"))
      (node (ref "C6") (pin "2") (pinfunction "2_2") (pintype "passive"))
      (node (ref "C60") (pin "1") (pinfunction "1_1") (pintype "passive"))
      (node (ref "C61") (pin "2") (pinfunction "2_2") (pintype "passive"))
      (node (ref "C62") (pin "2") (pinfunction "2_2") (pintype "passive"))
      (node (ref "C63") (pin "2") (pinfunction "2_2") (pintype "passive"))
      (node (ref "C64") (pin "2") (pinfunction "2_2") (pintype "passive"))
      (node (ref "C7") (pin "2") (pinfunction "2_2") (pintype "passive"))
      (node (ref "C8") (pin "2") (pinfunction "2_2") (pintype "passive"))
      (node (ref "C9") (pin "2") (pinfunction "2_2") (pintype "passive"))
      (node (ref "D2") (pin "A") (pinfunction "A_A") (pintype "passive"))
      (node (ref "D4") (pin "1") (pinfunction "A1_1") (pintype "passive"))
      (node (ref "D5") (pin "1") (pinfunction "A1_1") (pintype "passive"))
      (node (ref "GND") (pin "P$1") (pinfunction "P$1_P$1") (pintype "bidirectional"))
      (node (ref "IC1") (pin "11") (pinfunction "V-_11") (pintype "power_in"))
      (node (ref "IC2") (pin "11") (pinfunction "V-_11") (pintype "power_in"))
      (node (ref "LED1") (pin "COMMON") (pinfunction "COMMON_COMMON") (pintype "passive"))
      (node (ref "Q1") (pin "2") (pinfunction "S_2") (pintype "passive"))
      (node (ref "Q3") (pin "3") (pinfunction "C_3") (pintype "passive"))
      (node (ref "Q4") (pin "2") (pinfunction "E_2") (pintype "passive"))
      (node (ref "Q5") (pin "2") (pinfunction "E_2") (pintype "passive"))
      (node (ref "Q6") (pin "2") (pinfunction "E_2") (pintype "passive"))
      (node (ref "Q7") (pin "2") (pinfunction "E_2") (pintype "passive"))
      (node (ref "QZ2") (pin "2") (pinfunction "GND_2") (pintype "passive"))
      (node (ref "QZ2") (pin "4") (pinfunction "GND_4") (pintype "passive"))
      (node (ref "R15") (pin "1") (pinfunction "1_1") (pintype "passive"))
      (node (ref "R19") (pin "1") (pinfunction "1_1") (pintype "passive"))
      (node (ref "R2") (pin "1") (pinfunction "1_1") (pintype "passive"))
      (node (ref "R26") (pin "1") (pinfunction "1_1") (pintype "passive"))
      (node (ref "SWD") (pin "5") (pinfunction "5_5") (pintype "passive"))
      (node (ref "U1") (pin "2") (pinfunction "GND_2") (pintype "bidirectional"))
      (node (ref "U2") (pin "1") (pinfunction "GND_1") (pintype "bidirectional"))
      (node (ref "U3") (pin "10") (pinfunction "GND_10") (pintype "power_in"))
      (node (ref "U3") (pin "28") (pinfunction "GND_28") (pintype "power_in"))
      (node (ref "U4") (pin "10") (pinfunction "TVSS_10") (pintype "bidirectional"))
      (node (ref "U4") (pin "14") (pinfunction "TVSS_14") (pintype "bidirectional"))
      (node (ref "U4") (pin "18") (pinfunction "AVSS_18") (pintype "bidirectional"))
      (node (ref "U4") (pin "28") (pinfunction "D4_28") (pintype "bidirectional"))
      (node (ref "U4") (pin "29") (pinfunction "D5_29") (pintype "bidirectional"))
      (node (ref "U4") (pin "30") (pinfunction "D6_30") (pintype "bidirectional"))
      (node (ref "U4") (pin "32") (pinfunction "EA_32") (pintype "bidirectional"))
      (node (ref "U4") (pin "33") (pinfunction "PAD_33") (pintype "bidirectional"))
      (node (ref "U4") (pin "4") (pinfunction "DVSS_4") (pintype "bidirectional"))
      (node (ref "U4") (pin "5") (pinfunction "PVSS_5") (pintype "bidirectional"))
    )
    (net (code "15") (name "LED-GRN-CTRL") (class "Default")
      (node (ref "R53") (pin "1") (pinfunction "1_1") (pintype "passive"))
      (node (ref "U3") (pin "4") (pinfunction "PA3_4") (pintype "bidirectional"))
    )
    (net (code "16") (name "LED-INPUT") (class "Default")
      (node (ref "C63") (pin "1") (pinfunction "1_1") (pintype "passive"))
      (node (ref "D4") (pin "3") (pinfunction "C1A2_3") (pintype "passive"))
      (node (ref "R60") (pin "1") (pinfunction "1_1") (pintype "passive"))
      (node (ref "U3") (pin "14") (pinfunction "PA11_14") (pintype "bidirectional"))
    )
    (net (code "17") (name "LED-RED-CTRL") (class "Default")
      (node (ref "R54") (pin "2") (pinfunction "2_2") (pintype "passive"))
      (node (ref "U3") (pin "3") (pinfunction "PA2_3") (pintype "bidirectional"))
    )
    (net (code "18") (name "MIFARE-RST") (class "Default")
      (node (ref "U3") (pin "17") (pinfunction "PA16_17") (pintype "bidirectional"))
      (node (ref "U4") (pin "6") (pinfunction "NRSTPD_6") (pintype "bidirectional"))
    )
    (net (code "19") (name "MIFARE-RX") (class "Default")
      (node (ref "C51") (pin "2") (pinfunction "2_2") (pintype "passive"))
      (node (ref "R44") (pin "1") (pinfunction "1_1") (pintype "passive"))
      (node (ref "U4") (pin "17") (pinfunction "RX_17") (pintype "bidirectional"))
    )
    (net (code "20") (name "MIFARE-SCL") (class "Default")
      (node (ref "R42") (pin "1") (pinfunction "1_1") (pintype "passive"))
      (node (ref "U3") (pin "22") (pinfunction "PA23_22") (pintype "bidirectional"))
      (node (ref "U4") (pin "31") (pinfunction "D7_31") (pintype "bidirectional"))
    )
    (net (code "21") (name "MIFARE-SDA") (class "Default")
      (node (ref "R43") (pin "1") (pinfunction "1_1") (pintype "passive"))
      (node (ref "U3") (pin "21") (pinfunction "PA22_21") (pintype "bidirectional"))
      (node (ref "U4") (pin "24") (pinfunction "SDA_24") (pintype "bidirectional"))
    )
    (net (code "22") (name "MIFARE-TX1") (class "Default")
      (node (ref "L4") (pin "1") (pinfunction "1_1") (pintype "passive"))
      (node (ref "U4") (pin "11") (pinfunction "TX1_11") (pintype "bidirectional"))
    )
    (net (code "23") (name "MIFARE-TX2") (class "Default")
      (node (ref "L3") (pin "1") (pinfunction "1_1") (pintype "passive"))
      (node (ref "U4") (pin "13") (pinfunction "TX2_13") (pintype "bidirectional"))
    )
    (net (code "24") (name "Net-(C18-Pad1)") (class "Default")
      (node (ref "C18") (pin "1") (pinfunction "1_1") (pintype "passive"))
      (node (ref "R5") (pin "2") (pinfunction "2_2") (pintype "passive"))
    )
    (net (code "25") (name "Net-(C19-Pad1)") (class "Default")
      (node (ref "C19") (pin "1") (pinfunction "1_1") (pintype "passive"))
      (node (ref "R11") (pin "2") (pinfunction "2_2") (pintype "passive"))
      (node (ref "R12") (pin "2") (pinfunction "2_2") (pintype "passive"))
      (node (ref "R5") (pin "1") (pinfunction "1_1") (pintype "passive"))
    )
    (net (code "26") (name "Net-(C20-Pad1)") (class "Default")
      (node (ref "C20") (pin "1") (pinfunction "1_1") (pintype "passive"))
      (node (ref "R13") (pin "1") (pinfunction "1_1") (pintype "passive"))
      (node (ref "R14") (pin "2") (pinfunction "2_2") (pintype "passive"))
      (node (ref "R7") (pin "2") (pinfunction "2_2") (pintype "passive"))
    )
    (net (code "27") (name "Net-(C27-Pad1)") (class "Default")
      (node (ref "C27") (pin "1") (pinfunction "1_1") (pintype "passive"))
      (node (ref "C28") (pin "1") (pinfunction "1_1") (pintype "passive"))
      (node (ref "D3") (pin "K") (pinfunction "K_K") (pintype "passive"))
      (node (ref "R15") (pin "2") (pinfunction "2_2") (pintype "passive"))
    )
    (net (code "28") (name "Net-(C27-Pad2)") (class "Default")
      (node (ref "C27") (pin "2") (pinfunction "2_2") (pintype "passive"))
      (node (ref "R16") (pin "1") (pinfunction "1_1") (pintype "passive"))
      (node (ref "R17") (pin "2") (pinfunction "2_2") (pintype "passive"))
    )
    (net (code "29") (name "Net-(C29-Pad1)") (class "Default")
      (node (ref "C29") (pin "1") (pinfunction "1_1") (pintype "passive"))
      (node (ref "R21") (pin "1") (pinfunction "1_1") (pintype "passive"))
    )
    (net (code "30") (name "Net-(C30-Pad1)") (class "Default")
      (node (ref "C30") (pin "1") (pinfunction "1_1") (pintype "passive"))
      (node (ref "R20") (pin "2") (pinfunction "2_2") (pintype "passive"))
      (node (ref "R22") (pin "2") (pinfunction "2_2") (pintype "passive"))
      (node (ref "R25") (pin "1") (pinfunction "1_1") (pintype "passive"))
    )
    (net (code "31") (name "Net-(C31-Pad2)") (class "Default")
      (node (ref "C31") (pin "2") (pinfunction "2_2") (pintype "passive"))
      (node (ref "C32") (pin "2") (pinfunction "2_2") (pintype "passive"))
      (node (ref "R21") (pin "2") (pinfunction "2_2") (pintype "passive"))
      (node (ref "R23") (pin "2") (pinfunction "2_2") (pintype "passive"))
    )
    (net (code "32") (name "Net-(C35-Pad2)") (class "Default")
      (node (ref "C35") (pin "2") (pinfunction "2_2") (pintype "passive"))
      (node (ref "R35") (pin "2") (pinfunction "2_2") (pintype "passive"))
    )
    (net (code "33") (name "Net-(C36-Pad1)") (class "Default")
      (node (ref "C36") (pin "1") (pinfunction "1_1") (pintype "passive"))
      (node (ref "C41") (pin "2") (pinfunction "2_2") (pintype "passive"))
      (node (ref "R32") (pin "1") (pinfunction "1_1") (pintype "passive"))
      (node (ref "R34") (pin "1") (pinfunction "1_1") (pintype "passive"))
    )
    (net (code "34") (name "Net-(C37-Pad1)") (class "Default")
      (node (ref "C37") (pin "1") (pinfunction "1_1") (pintype "passive"))
      (node (ref "C40") (pin "1") (pinfunction "1_1") (pintype "passive"))
      (node (ref "R30") (pin "2") (pinfunction "2_2") (pintype "passive"))
      (node (ref "R37") (pin "1") (pinfunction "1_1") (pintype "passive"))
    )
    (net (code "35") (name "Net-(C37-Pad2)") (class "Default")
      (node (ref "C37") (pin "2") (pinfunction "2_2") (pintype "passive"))
      (node (ref "C40") (pin "2") (pinfunction "2_2") (pintype "passive"))
      (node (ref "R29") (pin "1") (pinfunction "1_1") (pintype "passive"))
      (node (ref "R32") (pin "2") (pinfunction "2_2") (pintype "passive"))
      (node (ref "R34") (pin "2") (pinfunction "2_2") (pintype "passive"))
      (node (ref "R38") (pin "2") (pinfunction "2_2") (pintype "passive"))
    )
    (net (code "36") (name "Net-(C38-Pad2)") (class "Default")
      (node (ref "C38") (pin "2") (pinfunction "2_2") (pintype "passive"))
      (node (ref "C39") (pin "2") (pinfunction "2_2") (pintype "passive"))
      (node (ref "R36") (pin "2") (pinfunction "2_2") (pintype "passive"))
      (node (ref "R40") (pin "2") (pinfunction "2_2") (pintype "passive"))
    )
    (net (code "37") (name "Net-(C43-Pad2)") (class "Default")
      (node (ref "C43") (pin "2") (pinfunction "2_2") (pintype "passive"))
      (node (ref "C44") (pin "2") (pinfunction "2_2") (pintype "passive"))
      (node (ref "R35") (pin "1") (pinfunction "1_1") (pintype "passive"))
      (node (ref "R39") (pin "2") (pinfunction "2_2") (pintype "passive"))
    )
    (net (code "38") (name "Net-(C45-Pad1)") (class "Default")
      (node (ref "C45") (pin "1") (pinfunction "1_1") (pintype "passive"))
      (node (ref "R40") (pin "1") (pinfunction "1_1") (pintype "passive"))
    )
    (net (code "39") (name "Net-(C51-Pad1)") (class "Default")
      (node (ref "C51") (pin "1") (pinfunction "1_1") (pintype "passive"))
      (node (ref "R45") (pin "2") (pinfunction "2_2") (pintype "passive"))
    )
    (net (code "40") (name "Net-(C54-Pad1)") (class "Default")
      (node (ref "C54") (pin "1") (pinfunction "1_1") (pintype "passive"))
      (node (ref "C56") (pin "2") (pinfunction "2_2") (pintype "passive"))
      (node (ref "L3") (pin "2") (pinfunction "2_2") (pintype "passive"))
    )
    (net (code "41") (name "Net-(C55-Pad2)") (class "Default")
      (node (ref "C55") (pin "2") (pinfunction "2_2") (pintype "passive"))
      (node (ref "C57") (pin "2") (pinfunction "2_2") (pintype "passive"))
      (node (ref "L4") (pin "2") (pinfunction "2_2") (pintype "passive"))
      (node (ref "R45") (pin "1") (pinfunction "1_1") (pintype "passive"))
    )
    (net (code "42") (name "Net-(C56-Pad1)") (class "Default")
      (node (ref "C56") (pin "1") (pinfunction "1_1") (pintype "passive"))
      (node (ref "C59") (pin "1") (pinfunction "1_1") (pintype "passive"))
      (node (ref "R46") (pin "1") (pinfunction "1_1") (pintype "passive"))
    )
    (net (code "43") (name "Net-(C57-Pad1)") (class "Default")
      (node (ref "C57") (pin "1") (pinfunction "1_1") (pintype "passive"))
      (node (ref "C60") (pin "2") (pinfunction "2_2") (pintype "passive"))
      (node (ref "R47") (pin "1") (pinfunction "1_1") (pintype "passive"))
    )
    (net (code "44") (name "Net-(CARDPRS-PadP$1)") (class "Default")
      (node (ref "CARDPRS") (pin "P$1") (pinfunction "P$1_P$1") (pintype "bidirectional"))
      (node (ref "R64") (pin "1") (pinfunction "1_1") (pintype "passive"))
    )
    (net (code "45") (name "Net-(D0/TX/CLK-PadP$1)") (class "Default")
      (node (ref "D0/TX/CLK") (pin "P$1") (pinfunction "P$1_P$1") (pintype "bidirectional"))
      (node (ref "R52") (pin "1") (pinfunction "1_1") (pintype "passive"))
    )
    (net (code "46") (name "Net-(D1/DATA-PadP$1)") (class "Default")
      (node (ref "D1/DATA") (pin "P$1") (pinfunction "P$1_P$1") (pintype "bidirectional"))
      (node (ref "R57") (pin "1") (pinfunction "1_1") (pintype "passive"))
    )
    (net (code "47") (name "Net-(IC1A-+IN)") (class "Default")
      (node (ref "IC1") (pin "3") (pinfunction "+IN_3") (pintype "input"))
      (node (ref "R17") (pin "1") (pinfunction "1_1") (pintype "passive"))
    )
    (net (code "48") (name "Net-(IC1A--IN)") (class "Default")
      (node (ref "IC1") (pin "1") (pinfunction "OUT_1") (pintype "output"))
      (node (ref "IC1") (pin "2") (pinfunction "-IN_2") (pintype "input"))
      (node (ref "R20") (pin "1") (pinfunction "1_1") (pintype "passive"))
    )
    (net (code "49") (name "Net-(IC1B--IN)") (class "Default")
      (node (ref "C33") (pin "2") (pinfunction "2_2") (pintype "passive"))
      (node (ref "IC1") (pin "6") (pinfunction "-IN_6") (pintype "input"))
      (node (ref "R25") (pin "2") (pinfunction "2_2") (pintype "passive"))
    )
    (net (code "50") (name "Net-(IC1C--IN)") (class "Default")
      (node (ref "C23") (pin "2") (pinfunction "2_2") (pintype "passive"))
      (node (ref "IC1") (pin "9") (pinfunction "-IN_9") (pintype "input"))
      (node (ref "R12") (pin "1") (pinfunction "1_1") (pintype "passive"))
    )
    (net (code "51") (name "Net-(IC1C-OUT)") (class "Default")
      (node (ref "C23") (pin "1") (pinfunction "1_1") (pintype "passive"))
      (node (ref "C26") (pin "1") (pinfunction "1_1") (pintype "passive"))
      (node (ref "IC1") (pin "8") (pinfunction "OUT_8") (pintype "output"))
      (node (ref "R11") (pin "1") (pinfunction "1_1") (pintype "passive"))
    )
    (net (code "52") (name "Net-(IC1D--IN)") (class "Default")
      (node (ref "C24") (pin "1") (pinfunction "1_1") (pintype "passive"))
      (node (ref "IC1") (pin "13") (pinfunction "-IN_13") (pintype "input"))
      (node (ref "R14") (pin "1") (pinfunction "1_1") (pintype "passive"))
    )
    (net (code "53") (name "Net-(IC1D-OUT)") (class "Default")
      (node (ref "C24") (pin "2") (pinfunction "2_2") (pintype "passive"))
      (node (ref "IC1") (pin "14") (pinfunction "OUT_14") (pintype "output"))
      (node (ref "R13") (pin "2") (pinfunction "2_2") (pintype "passive"))
      (node (ref "R18") (pin "1") (pinfunction "1_1") (pintype "passive"))
    )
    (net (code "54") (name "Net-(IC1E-V+)") (class "Default")
      (node (ref "C34") (pin "1") (pinfunction "1_1") (pintype "passive"))
      (node (ref "IC1") (pin "4") (pinfunction "V+_4") (pintype "power_in"))
      (node (ref "R24") (pin "2") (pinfunction "2_2") (pintype "passive"))
    )
    (net (code "55") (name "Net-(IC2A-+IN)") (class "Default")
      (node (ref "C41") (pin "1") (pinfunction "1_1") (pintype "passive"))
      (node (ref "IC2") (pin "3") (pinfunction "+IN_3") (pintype "input"))
      (node (ref "R37") (pin "2") (pinfunction "2_2") (pintype "passive"))
    )
    (net (code "56") (name "Net-(IC2B--IN)") (class "Default")
      (node (ref "C32") (pin "1") (pinfunction "1_1") (pintype "passive"))
      (node (ref "IC2") (pin "6") (pinfunction "-IN_6") (pintype "input"))
      (node (ref "R27") (pin "1") (pinfunction "1_1") (pintype "passive"))
    )
    (net (code "57") (name "Net-(IC2B-OUT)") (class "Default")
      (node (ref "C31") (pin "1") (pinfunction "1_1") (pintype "passive"))
      (node (ref "C35") (pin "1") (pinfunction "1_1") (pintype "passive"))
      (node (ref "IC2") (pin "7") (pinfunction "OUT_7") (pintype "output"))
      (node (ref "R27") (pin "2") (pinfunction "2_2") (pintype "passive"))
    )
    (net (code "58") (name "Net-(IC2C--IN)") (class "Default")
      (node (ref "C44") (pin "1") (pinfunction "1_1") (pintype "passive"))
      (node (ref "IC2") (pin "9") (pinfunction "-IN_9") (pintype "input"))
      (node (ref "R41") (pin "2") (pinfunction "2_2") (pintype "passive"))
    )
    (net (code "59") (name "Net-(IC2C-OUT)") (class "Default")
      (node (ref "C43") (pin "1") (pinfunction "1_1") (pintype "passive"))
      (node (ref "C45") (pin "2") (pinfunction "2_2") (pintype "passive"))
      (node (ref "IC2") (pin "8") (pinfunction "OUT_8") (pintype "output"))
      (node (ref "R41") (pin "1") (pinfunction "1_1") (pintype "passive"))
    )
    (net (code "60") (name "Net-(IC2D--IN)") (class "Default")
      (node (ref "C39") (pin "1") (pinfunction "1_1") (pintype "passive"))
      (node (ref "IC2") (pin "13") (pinfunction "-IN_13") (pintype "input"))
      (node (ref "R31") (pin "2") (pinfunction "2_2") (pintype "passive"))
    )
    (net (code "61") (name "Net-(IC2D-OUT)") (class "Default")
      (node (ref "C38") (pin "1") (pinfunction "1_1") (pintype "passive"))
      (node (ref "IC2") (pin "14") (pinfunction "OUT_14") (pintype "output"))
      (node (ref "R28") (pin "1") (pinfunction "1_1") (pintype "passive"))
      (node (ref "R31") (pin "1") (pinfunction "1_1") (pintype "passive"))
    )
    (net (code "62") (name "Net-(IC2E-V+)") (class "Default")
      (node (ref "C42") (pin "1") (pinfunction "1_1") (pintype "passive"))
      (node (ref "IC2") (pin "4") (pinfunction "V+_4") (pintype "power_in"))
      (node (ref "R33") (pin "2") (pinfunction "2_2") (pintype "passive"))
    )
    (net (code "63") (name "Net-(LED-IN-PadP$1)") (class "Default")
      (node (ref "LED-IN") (pin "P$1") (pinfunction "P$1_P$1") (pintype "bidirectional"))
      (node (ref "R58") (pin "2") (pinfunction "2_2") (pintype "passive"))
      (node (ref "R60") (pin "2") (pinfunction "2_2") (pintype "passive"))
    )
    (net (code "64") (name "Net-(LED1-PadANODE_GRN)") (class "Default")
      (node (ref "LED1") (pin "ANODE_GRN") (pinfunction "ANODE_GRN_ANODE_GRN") (pintype "passive"))
      (node (ref "R54") (pin "1") (pinfunction "1_1") (pintype "passive"))
    )
    (net (code "65") (name "Net-(LED1-PadANODE_RED)") (class "Default")
      (node (ref "LED1") (pin "ANODE_RED") (pinfunction "ANODE_RED_ANODE_RED") (pintype "passive"))
      (node (ref "R53") (pin "2") (pinfunction "2_2") (pintype "passive"))
    )
    (net (code "66") (name "Net-(MODE-PadP$1)") (class "Default")
      (node (ref "MODE") (pin "P$1") (pinfunction "P$1_P$1") (pintype "bidirectional"))
      (node (ref "R59") (pin "2") (pinfunction "2_2") (pintype "passive"))
      (node (ref "R61") (pin "2") (pinfunction "2_2") (pintype "passive"))
    )
    (net (code "67") (name "Net-(Q1-D)") (class "Default")
      (node (ref "Q1") (pin "3") (pinfunction "D_3") (pintype "passive"))
      (node (ref "Q2") (pin "1") (pinfunction "B_1") (pintype "passive"))
      (node (ref "Q3") (pin "1") (pinfunction "B_1") (pintype "passive"))
      (node (ref "R6") (pin "1") (pinfunction "1_1") (pintype "passive"))
    )
    (net (code "68") (name "Net-(Q1-G)") (class "Default")
      (node (ref "Q1") (pin "1") (pinfunction "G_1") (pintype "passive"))
      (node (ref "R4") (pin "2") (pinfunction "2_2") (pintype "passive"))
    )
    (net (code "69") (name "Net-(Q2-C)") (class "Default")
      (node (ref "C21") (pin "1") (pinfunction "1_1") (pintype "passive"))
      (node (ref "Q2") (pin "3") (pinfunction "C_3") (pintype "passive"))
      (node (ref "R8") (pin "1") (pinfunction "1_1") (pintype "passive"))
    )
    (net (code "70") (name "Net-(Q2-E)") (class "Default")
      (node (ref "Q2") (pin "2") (pinfunction "E_2") (pintype "passive"))
      (node (ref "R9") (pin "2") (pinfunction "2_2") (pintype "passive"))
    )
    (net (code "71") (name "Net-(Q3-E)") (class "Default")
      (node (ref "Q3") (pin "2") (pinfunction "E_2") (pintype "passive"))
      (node (ref "R10") (pin "1") (pinfunction "1_1") (pintype "passive"))
    )
    (net (code "72") (name "Net-(Q4-B)") (class "Default")
      (node (ref "Q4") (pin "1") (pinfunction "B_1") (pintype "passive"))
      (node (ref "R48") (pin "1") (pinfunction "1_1") (pintype "passive"))
    )
    (net (code "73") (name "Net-(Q4-C)") (class "Default")
      (node (ref "BZ1") (pin "-") (pinfunction "-_-") (pintype "passive"))
      (node (ref "Q4") (pin "3") (pinfunction "C_3") (pintype "passive"))
      (node (ref "R50") (pin "1") (pinfunction "1_1") (pintype "passive"))
    )
    (net (code "74") (name "Net-(Q5-B)") (class "Default")
      (node (ref "Q5") (pin "1") (pinfunction "B_1") (pintype "passive"))
      (node (ref "R49") (pin "1") (pinfunction "1_1") (pintype "passive"))
    )
    (net (code "75") (name "Net-(Q5-C)") (class "Default")
      (node (ref "Q5") (pin "3") (pinfunction "C_3") (pintype "passive"))
      (node (ref "R51") (pin "1") (pinfunction "1_1") (pintype "passive"))
      (node (ref "R52") (pin "2") (pinfunction "2_2") (pintype "passive"))
    )
    (net (code "76") (name "Net-(Q6-B)") (class "Default")
      (node (ref "Q6") (pin "1") (pinfunction "B_1") (pintype "passive"))
      (node (ref "R55") (pin "1") (pinfunction "1_1") (pintype "passive"))
    )
    (net (code "77") (name "Net-(Q6-C)") (class "Default")
      (node (ref "Q6") (pin "3") (pinfunction "C_3") (pintype "passive"))
      (node (ref "R56") (pin "1") (pinfunction "1_1") (pintype "passive"))
      (node (ref "R57") (pin "2") (pinfunction "2_2") (pintype "passive"))
    )
    (net (code "78") (name "Net-(Q7-B)") (class "Default")
      (node (ref "Q7") (pin "1") (pinfunction "B_1") (pintype "passive"))
      (node (ref "R62") (pin "1") (pinfunction "1_1") (pintype "passive"))
    )
    (net (code "79") (name "Net-(Q7-C)") (class "Default")
      (node (ref "Q7") (pin "3") (pinfunction "C_3") (pintype "passive"))
      (node (ref "R63") (pin "1") (pinfunction "1_1") (pintype "passive"))
      (node (ref "R64") (pin "2") (pinfunction "2_2") (pintype "passive"))
    )
    (net (code "80") (name "Net-(QZ2-2)") (class "Default")
      (node (ref "C46") (pin "1") (pinfunction "1_1") (pintype "passive"))
      (node (ref "QZ2") (pin "3") (pinfunction "2_3") (pintype "passive"))
      (node (ref "U4") (pin "21") (pinfunction "OSCIN_21") (pintype "bidirectional"))
    )
    (net (code "81") (name "Net-(U1-BYPASS)") (class "Default")
      (node (ref "C3") (pin "1") (pinfunction "1_1") (pintype "passive"))
      (node (ref "U1") (pin "4") (pinfunction "BYPASS_4") (pintype "bidirectional"))
    )
    (net (code "82") (name "Net-(U3B-VDDCORE)") (class "Default")
      (node (ref "C16") (pin "1") (pinfunction "1_1") (pintype "passive"))
      (node (ref "U3") (pin "29") (pinfunction "VDDCORE_29") (pintype "power_in"))
    )
    (net (code "83") (name "Net-(U4A-OSCOUT)") (class "Default")
      (node (ref "C47") (pin "1") (pinfunction "1_1") (pintype "passive"))
      (node (ref "QZ2") (pin "1") (pinfunction "1_1") (pintype "passive"))
      (node (ref "U4") (pin "22") (pinfunction "OSCOUT_22") (pintype "bidirectional"))
    )
    (net (code "84") (name "Net-(U4B-VMID)") (class "Default")
      (node (ref "C48") (pin "1") (pinfunction "1_1") (pintype "passive"))
      (node (ref "R44") (pin "2") (pinfunction "2_2") (pintype "passive"))
      (node (ref "U4") (pin "16") (pinfunction "VMID_16") (pintype "bidirectional"))
    )
    (net (code "85") (name "Net-(U4C-AVDD)") (class "Default")
      (node (ref "C53") (pin "1") (pinfunction "1_1") (pintype "passive"))
      (node (ref "L2") (pin "2") (pinfunction "2_2") (pintype "passive"))
      (node (ref "U4") (pin "15") (pinfunction "AVDD_15") (pintype "bidirectional"))
    )
    (net (code "86") (name "Net-(U4C-TVDD)") (class "Default")
      (node (ref "C52") (pin "1") (pinfunction "1_1") (pintype "passive"))
      (node (ref "L1") (pin "2") (pinfunction "2_2") (pintype "passive"))
      (node (ref "U4") (pin "12") (pinfunction "TVDD_12") (pintype "bidirectional"))
    )
    (net (code "87") (name "Net-(X1A-S)") (class "Default")
      (node (ref "R10") (pin "2") (pinfunction "2_2") (pintype "passive"))
      (node (ref "R9") (pin "1") (pinfunction "1_1") (pintype "passive"))
      (node (ref "X1") (pin "1") (pinfunction "S_1") (pintype "passive"))
    )
    (net (code "88") (name "Net-(X1B-S)") (class "Default")
      (node (ref "C22") (pin "1") (pinfunction "1_1") (pintype "passive"))
      (node (ref "D3") (pin "A") (pinfunction "A_A") (pintype "passive"))
      (node (ref "X1") (pin "2") (pinfunction "S_2") (pintype "passive"))
    )
    (net (code "89") (name "Net-(X2A-S)") (class "Default")
      (node (ref "R46") (pin "2") (pinfunction "2_2") (pintype "passive"))
      (node (ref "X2") (pin "1") (pinfunction "S_1") (pintype "passive"))
    )
    (net (code "90") (name "Net-(X2B-S)") (class "Default")
      (node (ref "R47") (pin "2") (pinfunction "2_2") (pintype "passive"))
      (node (ref "X2") (pin "2") (pinfunction "S_2") (pintype "passive"))
    )
    (net (code "91") (name "RESET") (class "Default")
      (node (ref "R3") (pin "1") (pinfunction "1_1") (pintype "passive"))
      (node (ref "SWD") (pin "4") (pinfunction "4_4") (pintype "passive"))
      (node (ref "U3") (pin "26") (pinfunction "RESET_26") (pintype "bidirectional"))
    )
    (net (code "92") (name "SWDCLK") (class "Default")
      (node (ref "SWD") (pin "3") (pinfunction "3_3") (pintype "passive"))
      (node (ref "U3") (pin "31") (pinfunction "PA30_31") (pintype "bidirectional"))
    )
    (net (code "93") (name "SWDIO") (class "Default")
      (node (ref "SWD") (pin "2") (pinfunction "2_2") (pintype "passive"))
      (node (ref "U3") (pin "32") (pinfunction "PA31_32") (pintype "bidirectional"))
    )
    (net (code "94") (name "USART-RX") (class "Default")
      (node (ref "C64") (pin "1") (pinfunction "1_1") (pintype "passive"))
      (node (ref "D5") (pin "3") (pinfunction "C1A2_3") (pintype "passive"))
      (node (ref "R61") (pin "1") (pinfunction "1_1") (pintype "passive"))
      (node (ref "U3") (pin "18") (pinfunction "PA17_18") (pintype "bidirectional"))
    )
    (net (code "95") (name "V+") (class "Default")
      (node (ref "C10") (pin "1") (pinfunction "1_1") (pintype "passive"))
      (node (ref "C11") (pin "1") (pinfunction "1_1") (pintype "passive"))
      (node (ref "C12") (pin "1") (pinfunction "1_1") (pintype "passive"))
      (node (ref "C25") (pin "1") (pinfunction "1_1") (pintype "passive"))
      (node (ref "C6") (pin "1") (pinfunction "1_1") (pintype "passive"))
      (node (ref "C7") (pin "1") (pinfunction "1_1") (pintype "passive"))
      (node (ref "C9") (pin "1") (pinfunction "1_1") (pintype "passive"))
      (node (ref "IC1") (pin "10") (pinfunction "+IN_10") (pintype "input"))
      (node (ref "IC1") (pin "12") (pinfunction "+IN_12") (pintype "input"))
      (node (ref "IC1") (pin "5") (pinfunction "+IN_5") (pintype "input"))
      (node (ref "IC2") (pin "10") (pinfunction "+IN_10") (pintype "input"))
      (node (ref "IC2") (pin "12") (pinfunction "+IN_12") (pintype "input"))
      (node (ref "IC2") (pin "5") (pinfunction "+IN_5") (pintype "input"))
      (node (ref "R1") (pin "2") (pinfunction "2_2") (pintype "passive"))
      (node (ref "R16") (pin "2") (pinfunction "2_2") (pintype "passive"))
      (node (ref "R2") (pin "2") (pinfunction "2_2") (pintype "passive"))
      (node (ref "R23") (pin "1") (pinfunction "1_1") (pintype "passive"))
      (node (ref "R29") (pin "2") (pinfunction "2_2") (pintype "passive"))
      (node (ref "R36") (pin "1") (pinfunction "1_1") (pintype "passive"))
      (node (ref "R39") (pin "1") (pinfunction "1_1") (pintype "passive"))
    )
    (net (code "96") (name "VCC{slash}2") (class "Default")
      (node (ref "D1") (pin "A") (pinfunction "A_A") (pintype "passive"))
      (node (ref "VCC") (pin "P$1") (pinfunction "P$1_P$1") (pintype "bidirectional"))
    )
    (net (code "97") (name "XIN") (class "Default")
      (node (ref "C13") (pin "1") (pinfunction "1_1") (pintype "passive"))
      (node (ref "QZ1") (pin "1") (pinfunction "1_1") (pintype "passive"))
      (node (ref "U3") (pin "15") (pinfunction "PA14_15") (pintype "bidirectional"))
    )
    (net (code "98") (name "XOUT") (class "Default")
      (node (ref "C15") (pin "1") (pinfunction "1_1") (pintype "passive"))
      (node (ref "QZ1") (pin "2") (pinfunction "2_2") (pintype "passive"))
      (node (ref "U3") (pin "16") (pinfunction "PA15_16") (pintype "bidirectional"))
    )
    (net (code "99") (name "unconnected-(U3A-PA6-Pad7)") (class "Default")
      (node (ref "U3") (pin "7") (pinfunction "PA6_7") (pintype "bidirectional"))
    )
    (net (code "100") (name "unconnected-(U3A-PA18-Pad19)") (class "Default")
      (node (ref "U3") (pin "19") (pinfunction "PA18_19") (pintype "bidirectional"))
    )
    (net (code "101") (name "unconnected-(U3A-PA19-Pad20)") (class "Default")
      (node (ref "U3") (pin "20") (pinfunction "PA19_20") (pintype "bidirectional"))
    )
    (net (code "102") (name "unconnected-(U3A-PA24-Pad23)") (class "Default")
      (node (ref "U3") (pin "23") (pinfunction "PA24_23") (pintype "bidirectional"))
    )
    (net (code "103") (name "unconnected-(U3A-PA27-Pad25)") (class "Default")
      (node (ref "U3") (pin "25") (pinfunction "PA27_25") (pintype "bidirectional"))
    )
    (net (code "104") (name "unconnected-(U3A-PA28-Pad27)") (class "Default")
      (node (ref "U3") (pin "27") (pinfunction "PA28_27") (pintype "bidirectional"))
    )
    (net (code "105") (name "unconnected-(U4A-AUX1-Pad19)") (class "Default")
      (node (ref "U4") (pin "19") (pinfunction "AUX1_19") (pintype "bidirectional"))
    )
    (net (code "106") (name "unconnected-(U4A-AUX2-Pad20)") (class "Default")
      (node (ref "U4") (pin "20") (pinfunction "AUX2_20") (pintype "bidirectional"))
    )
    (net (code "107") (name "unconnected-(U4B-D1-Pad25)") (class "Default")
      (node (ref "U4") (pin "25") (pinfunction "D1_25") (pintype "bidirectional"))
    )
    (net (code "108") (name "unconnected-(U4B-D2-Pad26)") (class "Default")
      (node (ref "U4") (pin "26") (pinfunction "D2_26") (pintype "bidirectional"))
    )
    (net (code "109") (name "unconnected-(U4B-D3-Pad27)") (class "Default")
      (node (ref "U4") (pin "27") (pinfunction "D3_27") (pintype "bidirectional"))
    )
    (net (code "110") (name "unconnected-(U4B-IRQ-Pad23)") (class "Default")
      (node (ref "U4") (pin "23") (pinfunction "IRQ_23") (pintype "bidirectional"))
    )
    (net (code "111") (name "unconnected-(U4B-MFIN-Pad7)") (class "Default")
      (node (ref "U4") (pin "7") (pinfunction "MFIN_7") (pintype "bidirectional"))
    )
    (net (code "112") (name "unconnected-(U4B-MFOUT-Pad8)") (class "Default")
      (node (ref "U4") (pin "8") (pinfunction "MFOUT_8") (pintype "bidirectional"))
    )
  )
)
